# FPGA.net
KiCad netlist of a schematic drawn in Altium Designer
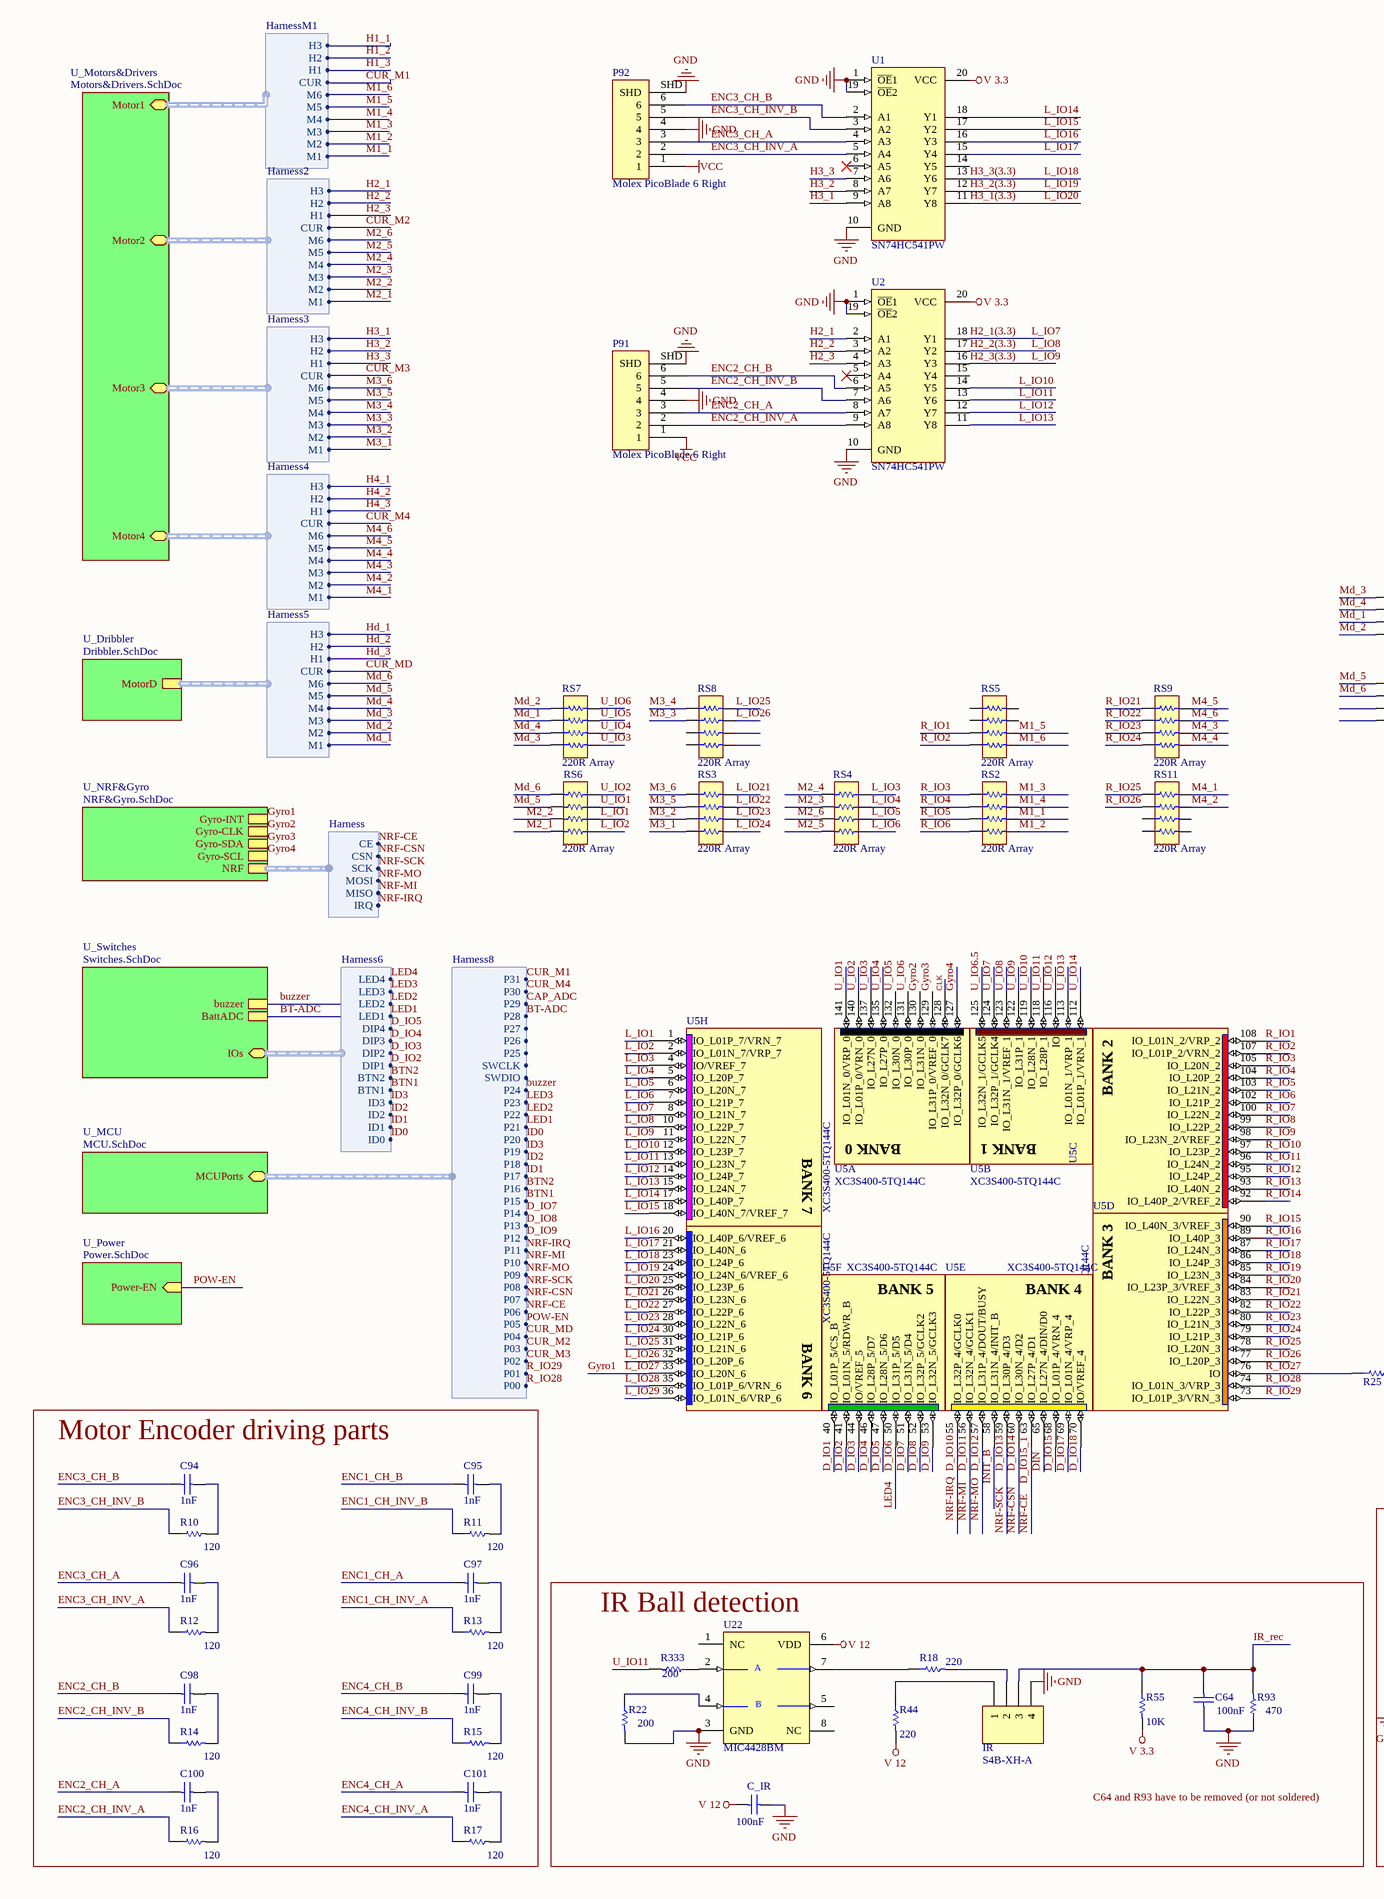
[diagram p0: FPGA.SchDoc, left]
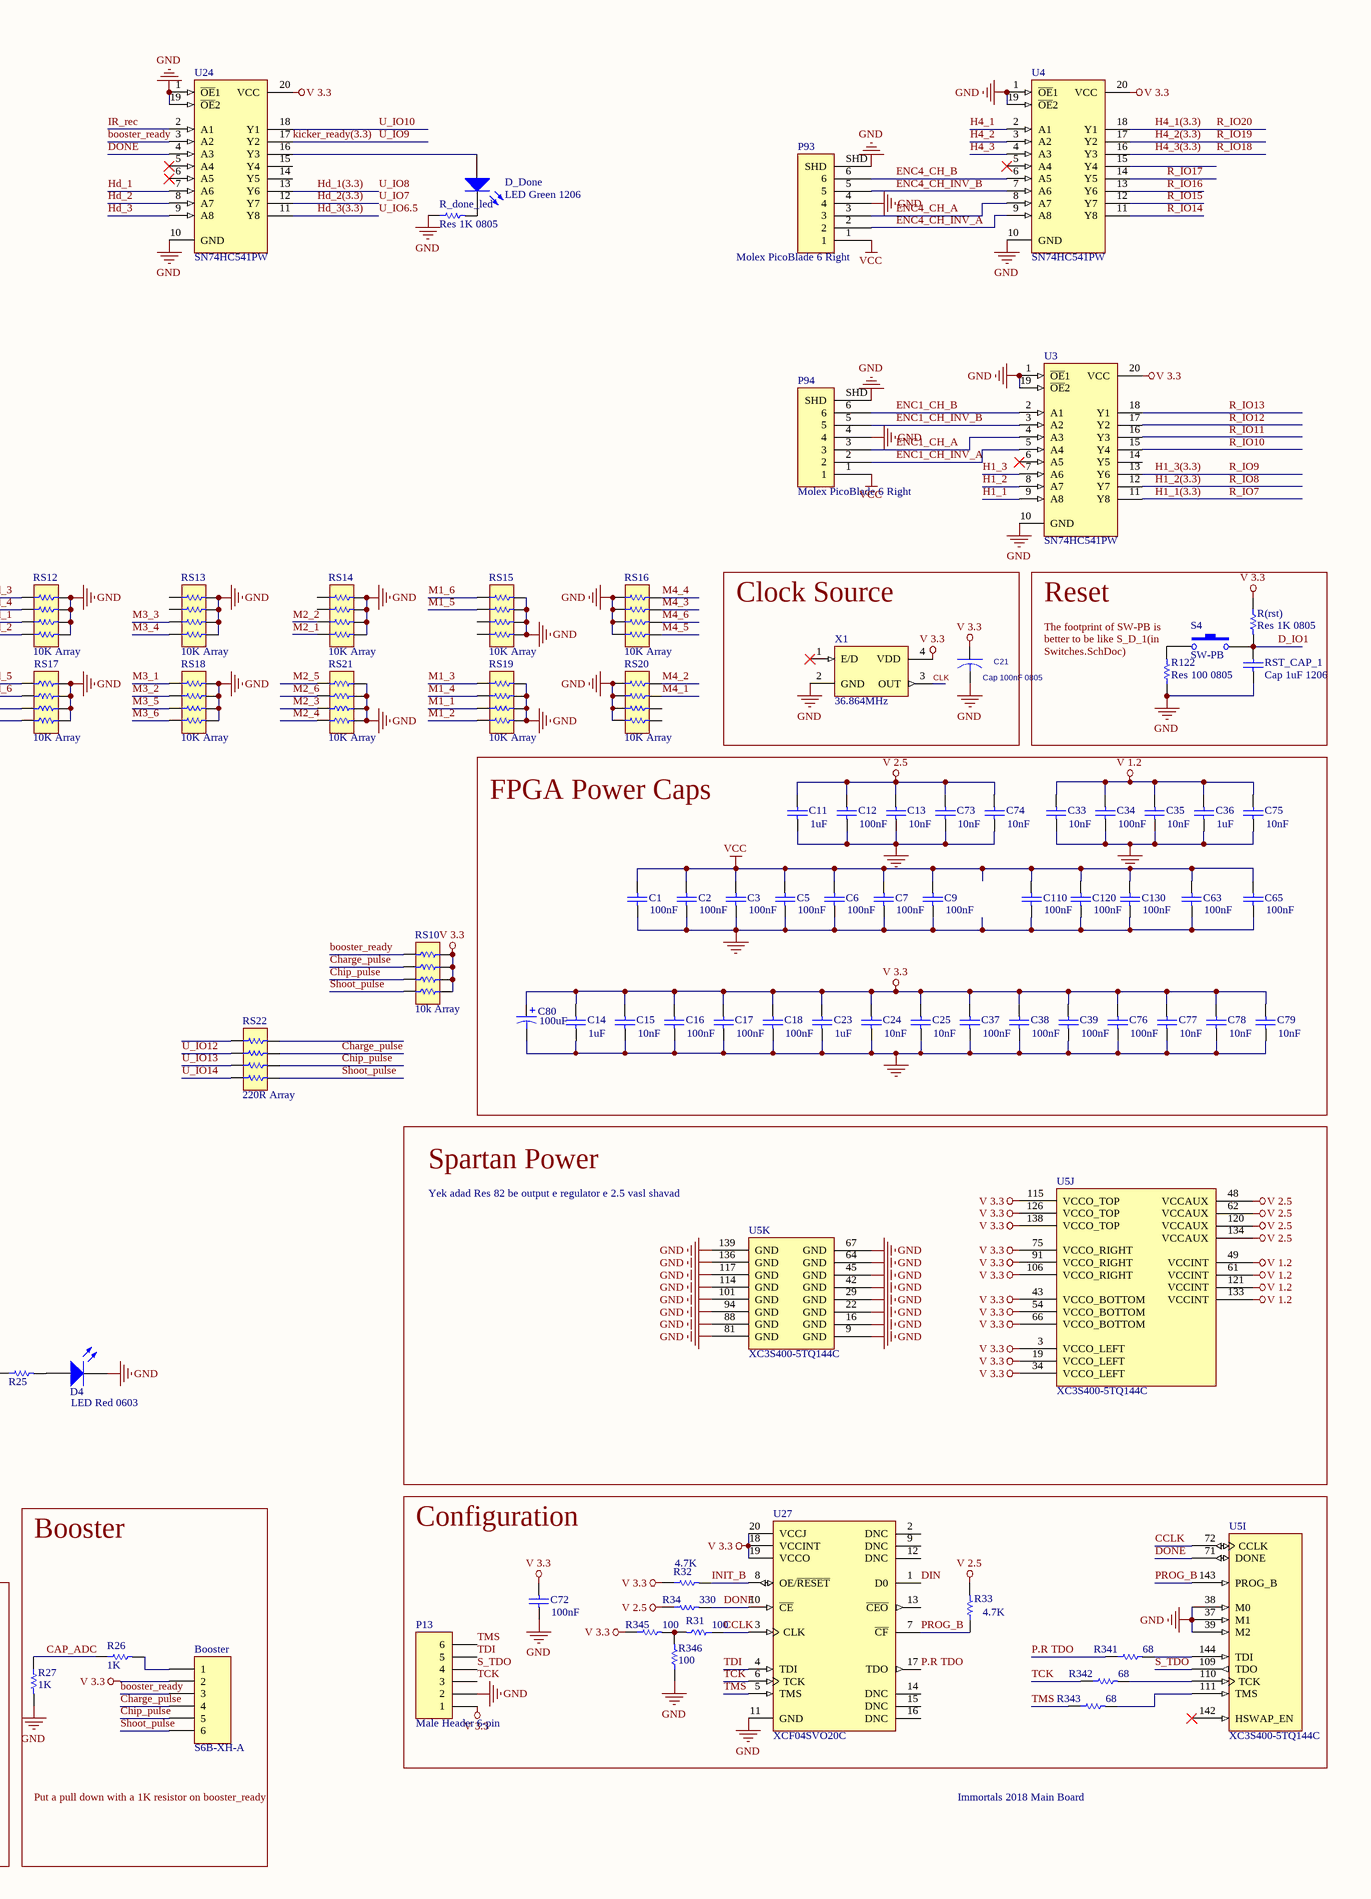
[diagram p1: FPGA.SchDoc, right]

(export (version "E")
  (design (tool "Eeschema 10.0.6"))
  (components
    (comp (ref "Booster")
      (value "S6B-XH-A")
      (footprint "S6B-XH-A")
      (description "Header, 6-Pin")
      (fields (field (name "PUBLISHER") "Altium Limited"))
      (libsource (lib "REV(5)") (part "Header 6"))
    )
    (comp (ref "C1")
      (value "100nF")
      (footprint "C1206")
      (description "Capacitor")
      (fields (field (name "Comment") "Cap 100nF 1206"))
      (libsource (lib "Altium Nanoboard Project") (part "CAP"))
    )
    (comp (ref "C2")
      (value "100nF")
      (footprint "C1206")
      (description "Capacitor")
      (fields (field (name "Comment") "Cap 100nF 1206"))
      (libsource (lib "Altium Nanoboard Project") (part "CAP"))
    )
    (comp (ref "C3")
      (value "100nF")
      (footprint "C1206")
      (description "Capacitor")
      (fields (field (name "Comment") "Cap 100nF 1206"))
      (libsource (lib "Altium Nanoboard Project") (part "CAP"))
    )
    (comp (ref "C5")
      (value "100nF")
      (footprint "C1206")
      (description "Capacitor")
      (fields (field (name "Comment") "Cap 100nF 1206"))
      (libsource (lib "Altium Nanoboard Project") (part "CAP"))
    )
    (comp (ref "C6")
      (value "100nF")
      (footprint "C1206")
      (description "Capacitor")
      (fields (field (name "Comment") "Cap 100nF 1206"))
      (libsource (lib "Altium Nanoboard Project") (part "CAP"))
    )
    (comp (ref "C7")
      (value "100nF")
      (footprint "C1206")
      (description "Capacitor")
      (fields (field (name "Comment") "Cap 100nF 1206"))
      (libsource (lib "Altium Nanoboard Project") (part "CAP"))
    )
    (comp (ref "C9")
      (value "100nF")
      (footprint "C1206")
      (description "Capacitor")
      (fields (field (name "Comment") "Cap 100nF 1206"))
      (libsource (lib "Altium Nanoboard Project") (part "CAP"))
    )
    (comp (ref "C11")
      (value "1uF")
      (footprint "1608[0603]")
      (description "Capacitor (Semiconductor SIM Model)")
      (fields (field (name "Comment") "Cap 1uF 0603") (field (name "PUBLISHER") "Altium Limited"))
      (libsource (lib "Miscellaneous Devices") (part "Cap Semi"))
    )
    (comp (ref "C12")
      (value "100nF")
      (footprint "1608[0603]")
      (description "Capacitor (Semiconductor SIM Model)")
      (fields (field (name "Comment") "Cap 100nF 0603") (field (name "PUBLISHER") "Altium Limited"))
      (libsource (lib "Miscellaneous Devices") (part "Cap Semi"))
    )
    (comp (ref "C13")
      (value "10nF")
      (footprint "1608[0603]")
      (description "Capacitor (Semiconductor SIM Model)")
      (fields (field (name "Comment") "Cap 10nF 0603") (field (name "PUBLISHER") "Altium Limited"))
      (libsource (lib "Miscellaneous Devices") (part "Cap Semi"))
    )
    (comp (ref "C14")
      (value "1uF")
      (footprint "1608[0603]")
      (description "Capacitor (Semiconductor SIM Model)")
      (fields (field (name "Comment") "Cap 1uF 0603") (field (name "PUBLISHER") "Altium Limited"))
      (libsource (lib "Miscellaneous Devices") (part "Cap Semi"))
    )
    (comp (ref "C15")
      (value "10nF")
      (footprint "1608[0603]")
      (description "Capacitor (Semiconductor SIM Model)")
      (fields (field (name "Comment") "Cap 10nF 0603") (field (name "PUBLISHER") "Altium Limited"))
      (libsource (lib "Miscellaneous Devices") (part "Cap Semi"))
    )
    (comp (ref "C16")
      (value "100nF")
      (footprint "1608[0603]")
      (description "Capacitor (Semiconductor SIM Model)")
      (fields (field (name "Comment") "Cap 100nF 0603") (field (name "PUBLISHER") "Altium Limited"))
      (libsource (lib "Miscellaneous Devices") (part "Cap Semi"))
    )
    (comp (ref "C17")
      (value "100nF")
      (footprint "1608[0603]")
      (description "Capacitor (Semiconductor SIM Model)")
      (fields (field (name "Comment") "Cap 100nF 0603") (field (name "PUBLISHER") "Altium Limited"))
      (libsource (lib "Miscellaneous Devices") (part "Cap Semi"))
    )
    (comp (ref "C18")
      (value "100nF")
      (footprint "1608[0603]")
      (description "Capacitor (Semiconductor SIM Model)")
      (fields (field (name "Comment") "Cap 100nF 0603") (field (name "PUBLISHER") "Altium Limited"))
      (libsource (lib "Miscellaneous Devices") (part "Cap Semi"))
    )
    (comp (ref "C21") (value "Cap 100nF 0805") (footprint "2012[0805]") (libsource (lib "*") (part "C_Dup1")))
    (comp (ref "C23")
      (value "1uF")
      (footprint "1608[0603]")
      (description "Capacitor (Semiconductor SIM Model)")
      (fields (field (name "Comment") "Cap 1uF 0603") (field (name "PUBLISHER") "Altium Limited"))
      (libsource (lib "Miscellaneous Devices") (part "Cap Semi"))
    )
    (comp (ref "C24")
      (value "10nF")
      (footprint "1608[0603]")
      (description "Capacitor (Semiconductor SIM Model)")
      (fields (field (name "Comment") "Cap 10nF 0603") (field (name "PUBLISHER") "Altium Limited"))
      (libsource (lib "Miscellaneous Devices") (part "Cap Semi"))
    )
    (comp (ref "C25")
      (value "10nF")
      (footprint "1608[0603]")
      (description "Capacitor (Semiconductor SIM Model)")
      (fields (field (name "Comment") "Cap 10nF 0603") (field (name "PUBLISHER") "Altium Limited"))
      (libsource (lib "Miscellaneous Devices") (part "Cap Semi"))
    )
    (comp (ref "C33")
      (value "10nF")
      (footprint "1608[0603]")
      (description "Capacitor (Semiconductor SIM Model)")
      (fields (field (name "Comment") "Cap 10nF 0603") (field (name "PUBLISHER") "Altium Limited"))
      (libsource (lib "Miscellaneous Devices") (part "Cap Semi"))
    )
    (comp (ref "C34")
      (value "100nF")
      (footprint "1608[0603]")
      (description "Capacitor (Semiconductor SIM Model)")
      (fields (field (name "Comment") "Cap 100nF 0603") (field (name "PUBLISHER") "Altium Limited"))
      (libsource (lib "Miscellaneous Devices") (part "Cap Semi"))
    )
    (comp (ref "C35")
      (value "10nF")
      (footprint "1608[0603]")
      (description "Capacitor (Semiconductor SIM Model)")
      (fields (field (name "Comment") "Cap 10nF 0603") (field (name "PUBLISHER") "Altium Limited"))
      (libsource (lib "Miscellaneous Devices") (part "Cap Semi"))
    )
    (comp (ref "C36")
      (value "1uF")
      (footprint "1608[0603]")
      (description "Capacitor (Semiconductor SIM Model)")
      (fields (field (name "Comment") "Cap 1uF 0603") (field (name "PUBLISHER") "Altium Limited"))
      (libsource (lib "Miscellaneous Devices") (part "Cap Semi"))
    )
    (comp (ref "C37")
      (value "100nF")
      (footprint "1608[0603]")
      (description "Capacitor (Semiconductor SIM Model)")
      (fields (field (name "Comment") "Cap 100nF 0603") (field (name "PUBLISHER") "Altium Limited"))
      (libsource (lib "Miscellaneous Devices") (part "Cap Semi"))
    )
    (comp (ref "C38")
      (value "100nF")
      (footprint "1608[0603]")
      (description "Capacitor (Semiconductor SIM Model)")
      (fields (field (name "Comment") "Cap 100nF 0603") (field (name "PUBLISHER") "Altium Limited"))
      (libsource (lib "Miscellaneous Devices") (part "Cap Semi"))
    )
    (comp (ref "C39")
      (value "100nF")
      (footprint "1608[0603]")
      (description "Capacitor (Semiconductor SIM Model)")
      (fields (field (name "Comment") "Cap 100nF 0603") (field (name "PUBLISHER") "Altium Limited"))
      (libsource (lib "Miscellaneous Devices") (part "Cap Semi"))
    )
    (comp (ref "C63")
      (value "100nF")
      (footprint "C0805")
      (description "Capacitor")
      (fields (field (name "Comment") "Cap 100nF 0805"))
      (libsource (lib "Altium Nanoboard Project") (part "CAP"))
    )
    (comp (ref "C64")
      (value "100nF")
      (footprint "1608[0603]")
      (description "Capacitor (Semiconductor SIM Model)")
      (fields (field (name "Comment") "Cap 100nF 0603") (field (name "PUBLISHER") "Altium Limited"))
      (libsource (lib "Miscellaneous Devices") (part "Cap Semi"))
    )
    (comp (ref "C65")
      (value "100nF")
      (footprint "C0805")
      (description "Capacitor")
      (fields (field (name "Comment") "Cap 100nF 0805"))
      (libsource (lib "Altium Nanoboard Project") (part "CAP"))
    )
    (comp (ref "C72")
      (value "100nF")
      (footprint "C0805")
      (description "Capacitor")
      (fields (field (name "Comment") "Cap 100nF 0805"))
      (libsource (lib "Altium Nanoboard Project") (part "CAP"))
    )
    (comp (ref "C73")
      (value "10nF")
      (footprint "1608[0603]")
      (description "Capacitor (Semiconductor SIM Model)")
      (fields (field (name "Comment") "Cap 10nF 0603") (field (name "PUBLISHER") "Altium Limited"))
      (libsource (lib "Miscellaneous Devices") (part "Cap Semi"))
    )
    (comp (ref "C74")
      (value "10nF")
      (footprint "1608[0603]")
      (description "Capacitor (Semiconductor SIM Model)")
      (fields (field (name "Comment") "Cap 10nF 0603") (field (name "PUBLISHER") "Altium Limited"))
      (libsource (lib "Miscellaneous Devices") (part "Cap Semi"))
    )
    (comp (ref "C75")
      (value "10nF")
      (footprint "1608[0603]")
      (description "Capacitor (Semiconductor SIM Model)")
      (fields (field (name "Comment") "Cap 10nF 0603") (field (name "PUBLISHER") "Altium Limited"))
      (libsource (lib "Miscellaneous Devices") (part "Cap Semi"))
    )
    (comp (ref "C76")
      (value "100nF")
      (footprint "1608[0603]")
      (description "Capacitor (Semiconductor SIM Model)")
      (fields (field (name "Comment") "Cap 100nF 0603") (field (name "PUBLISHER") "Altium Limited"))
      (libsource (lib "Miscellaneous Devices") (part "Cap Semi"))
    )
    (comp (ref "C77")
      (value "10nF")
      (footprint "1608[0603]")
      (description "Capacitor (Semiconductor SIM Model)")
      (fields (field (name "Comment") "Cap 10nF 0603") (field (name "PUBLISHER") "Altium Limited"))
      (libsource (lib "Miscellaneous Devices") (part "Cap Semi"))
    )
    (comp (ref "C78")
      (value "10nF")
      (footprint "1608[0603]")
      (description "Capacitor (Semiconductor SIM Model)")
      (fields (field (name "Comment") "Cap 10nF 0603") (field (name "PUBLISHER") "Altium Limited"))
      (libsource (lib "Miscellaneous Devices") (part "Cap Semi"))
    )
    (comp (ref "C79")
      (value "10nF")
      (footprint "1608[0603]")
      (description "Capacitor (Semiconductor SIM Model)")
      (fields (field (name "Comment") "Cap 10nF 0603") (field (name "PUBLISHER") "Altium Limited"))
      (libsource (lib "Miscellaneous Devices") (part "Cap Semi"))
    )
    (comp (ref "C80")
      (value "100uF")
      (footprint "6332[2512]")
      (description "Polarized Capacitor (Surface Mount)")
      (fields (field (name "Comment") "Cap 100uF 2512") (field (name "PUBLISHER") "Altium Limited"))
      (libsource (lib "Miscellaneous Devices") (part "Cap Pol3"))
    )
    (comp (ref "C94")
      (value "1nF")
      (footprint "1608[0603]")
      (description "Capacitor (Semiconductor SIM Model)")
      (fields (field (name "Comment") "Cap 1nF 0603") (field (name "PUBLISHER") "Altium Limited"))
      (libsource (lib "Miscellaneous Devices") (part "Cap Semi"))
    )
    (comp (ref "C95")
      (value "1nF")
      (footprint "1608[0603]")
      (description "Capacitor (Semiconductor SIM Model)")
      (fields (field (name "Comment") "Cap 1nF 0603") (field (name "PUBLISHER") "Altium Limited"))
      (libsource (lib "Miscellaneous Devices") (part "Cap Semi"))
    )
    (comp (ref "C96")
      (value "1nF")
      (footprint "1608[0603]")
      (description "Capacitor (Semiconductor SIM Model)")
      (fields (field (name "Comment") "Cap 1nF 0603") (field (name "PUBLISHER") "Altium Limited"))
      (libsource (lib "Miscellaneous Devices") (part "Cap Semi"))
    )
    (comp (ref "C97")
      (value "1nF")
      (footprint "1608[0603]")
      (description "Capacitor (Semiconductor SIM Model)")
      (fields (field (name "Comment") "Cap 1nF 0603") (field (name "PUBLISHER") "Altium Limited"))
      (libsource (lib "Miscellaneous Devices") (part "Cap Semi"))
    )
    (comp (ref "C98")
      (value "1nF")
      (footprint "1608[0603]")
      (description "Capacitor (Semiconductor SIM Model)")
      (fields (field (name "Comment") "Cap 1nF 0603") (field (name "PUBLISHER") "Altium Limited"))
      (libsource (lib "Miscellaneous Devices") (part "Cap Semi"))
    )
    (comp (ref "C99")
      (value "1nF")
      (footprint "1608[0603]")
      (description "Capacitor (Semiconductor SIM Model)")
      (fields (field (name "Comment") "Cap 1nF 0603") (field (name "PUBLISHER") "Altium Limited"))
      (libsource (lib "Miscellaneous Devices") (part "Cap Semi"))
    )
    (comp (ref "C100")
      (value "1nF")
      (footprint "1608[0603]")
      (description "Capacitor (Semiconductor SIM Model)")
      (fields (field (name "Comment") "Cap 1nF 0603") (field (name "PUBLISHER") "Altium Limited"))
      (libsource (lib "Miscellaneous Devices") (part "Cap Semi"))
    )
    (comp (ref "C101")
      (value "1nF")
      (footprint "1608[0603]")
      (description "Capacitor (Semiconductor SIM Model)")
      (fields (field (name "Comment") "Cap 1nF 0603") (field (name "PUBLISHER") "Altium Limited"))
      (libsource (lib "Miscellaneous Devices") (part "Cap Semi"))
    )
    (comp (ref "C110")
      (value "100nF")
      (footprint "C1206")
      (description "Capacitor")
      (fields (field (name "Comment") "Cap 100nF 1206"))
      (libsource (lib "Altium Nanoboard Project") (part "CAP"))
    )
    (comp (ref "C120")
      (value "100nF")
      (footprint "C1206")
      (description "Capacitor")
      (fields (field (name "Comment") "Cap 100nF 1206"))
      (libsource (lib "Altium Nanoboard Project") (part "CAP"))
    )
    (comp (ref "C130")
      (value "100nF")
      (footprint "C1206")
      (description "Capacitor")
      (fields (field (name "Comment") "Cap 100nF 1206"))
      (libsource (lib "Altium Nanoboard Project") (part "CAP"))
    )
    (comp (ref "C_IR")
      (value "100nF")
      (footprint "C0805")
      (description "Capacitor")
      (fields (field (name "Comment") "Cap 100nF 0805"))
      (libsource (lib "Altium Nanoboard Project") (part "CAP"))
    )
    (comp (ref "D4")
      (value "LED Red 0603")
      (footprint "LED 0603")
      (description "LED ,SMD ,0603")
      (fields (field (name "PUBLISHER") "Altium Limited"))
      (libsource (lib "SamatecLib") (part "LED 0603"))
    )
    (comp (ref "D_Done")
      (value "LED Green 1206")
      (footprint "3.2X1.6X1.1 - GREEN")
      (description "Typical RED, GREEN, YELLOW, AMBER GaAs LED")
      (fields (field (name "PUBLISHER") "Altium Limited"))
      (libsource (lib "Miscellaneous Devices") (part "LED2"))
    )
    (comp (ref "IR")
      (value "S4B-XH-A")
      (footprint "S4B-XH-A")
      (description "Header, 4-Pin")
      (fields (field (name "PUBLISHER") "Altium Limited"))
      (libsource (lib "REV(5)") (part "Header 4"))
    )
    (comp (ref "P13")
      (value "Male Header 6-pin")
      (footprint "HDR1X6")
      (description "Header, 6-Pin")
      (fields (field (name "PUBLISHER") "Altium Limited"))
      (libsource (lib "Miscellaneous Connectors") (part "Header 6"))
    )
    (comp (ref "P91")
      (value "Molex PicoBlade 6 Right")
      (footprint "Molex PicoBlade 6 Right SMD")
      (libsource (lib "SamatecLib") (part "Molex PicoBlade 6 Right"))
    )
    (comp (ref "P92")
      (value "Molex PicoBlade 6 Right")
      (footprint "Molex PicoBlade 6 Right SMD")
      (libsource (lib "SamatecLib") (part "Molex PicoBlade 6 Right"))
    )
    (comp (ref "P93")
      (value "Molex PicoBlade 6 Right")
      (footprint "Molex PicoBlade 6 Right SMD")
      (libsource (lib "SamatecLib") (part "Molex PicoBlade 6 Right"))
    )
    (comp (ref "P94")
      (value "Molex PicoBlade 6 Right")
      (footprint "Molex PicoBlade 6 Right SMD")
      (libsource (lib "SamatecLib") (part "Molex PicoBlade 6 Right"))
    )
    (comp (ref "R(rst)")
      (value "Res 1K 0805")
      (footprint "Miscellaneous Devices:2012[0805]")
      (description "Resistor")
      (fields (field (name "PUBLISHER") "Altium Limited"))
      (libsource (lib "Miscellaneous Devices") (part "Res1"))
    )
    (comp (ref "R10")
      (value "120")
      (footprint "1608[0603]")
      (description "Semiconductor Resistor")
      (fields (field (name "Comment") "Res 120 0603") (field (name "PUBLISHER") "Altium Limited"))
      (libsource (lib "Miscellaneous Devices") (part "Res Semi"))
    )
    (comp (ref "R11")
      (value "120")
      (footprint "1608[0603]")
      (description "Semiconductor Resistor")
      (fields (field (name "Comment") "Res 120 0603") (field (name "PUBLISHER") "Altium Limited"))
      (libsource (lib "Miscellaneous Devices") (part "Res Semi"))
    )
    (comp (ref "R12")
      (value "120")
      (footprint "1608[0603]")
      (description "Semiconductor Resistor")
      (fields (field (name "Comment") "Res 120 0603") (field (name "PUBLISHER") "Altium Limited"))
      (libsource (lib "Miscellaneous Devices") (part "Res Semi"))
    )
    (comp (ref "R13")
      (value "120")
      (footprint "1608[0603]")
      (description "Semiconductor Resistor")
      (fields (field (name "Comment") "Res 120 0603") (field (name "PUBLISHER") "Altium Limited"))
      (libsource (lib "Miscellaneous Devices") (part "Res Semi"))
    )
    (comp (ref "R14")
      (value "120")
      (footprint "1608[0603]")
      (description "Semiconductor Resistor")
      (fields (field (name "Comment") "Res 120 0603") (field (name "PUBLISHER") "Altium Limited"))
      (libsource (lib "Miscellaneous Devices") (part "Res Semi"))
    )
    (comp (ref "R15")
      (value "120")
      (footprint "1608[0603]")
      (description "Semiconductor Resistor")
      (fields (field (name "Comment") "Res 120 0603") (field (name "PUBLISHER") "Altium Limited"))
      (libsource (lib "Miscellaneous Devices") (part "Res Semi"))
    )
    (comp (ref "R16")
      (value "120")
      (footprint "1608[0603]")
      (description "Semiconductor Resistor")
      (fields (field (name "Comment") "Res 120 0603") (field (name "PUBLISHER") "Altium Limited"))
      (libsource (lib "Miscellaneous Devices") (part "Res Semi"))
    )
    (comp (ref "R17")
      (value "120")
      (footprint "1608[0603]")
      (description "Semiconductor Resistor")
      (fields (field (name "Comment") "Res 120 0603") (field (name "PUBLISHER") "Altium Limited"))
      (libsource (lib "Miscellaneous Devices") (part "Res Semi"))
    )
    (comp (ref "R18")
      (value "220")
      (footprint "2012[0805]")
      (description "Semiconductor Resistor")
      (fields (field (name "Comment") "Res 220 0805") (field (name "PUBLISHER") "Altium Limited"))
      (libsource (lib "Miscellaneous Devices") (part "Res Semi"))
    )
    (comp (ref "R22")
      (value "200")
      (footprint "2012[0805]")
      (description "Semiconductor Resistor")
      (fields (field (name "Comment") "Res 200 0805") (field (name "PUBLISHER") "Altium Limited"))
      (libsource (lib "Miscellaneous Devices") (part "Res Semi"))
    )
    (comp (ref "R25")
      (value "Res 330 0603")
      (footprint "R0603")
      (description "Res 0603")
      (libsource (lib "SamatecLib") (part "R0603"))
    )
    (comp (ref "R26")
      (value "1K")
      (footprint "2012[0805]")
      (description "Semiconductor Resistor")
      (fields (field (name "Comment") "Res 1K 0805") (field (name "PUBLISHER") "Altium Limited"))
      (libsource (lib "Miscellaneous Devices") (part "Res Semi"))
    )
    (comp (ref "R27")
      (value "1K")
      (footprint "2012[0805]")
      (description "Semiconductor Resistor")
      (fields (field (name "Comment") "Res 1K 0805") (field (name "PUBLISHER") "Altium Limited"))
      (libsource (lib "Miscellaneous Devices") (part "Res Semi"))
    )
    (comp (ref "R31")
      (value "100")
      (footprint "2012[0805]")
      (description "Semiconductor Resistor")
      (fields (field (name "Comment") "Res 100 0805") (field (name "PUBLISHER") "Altium Limited"))
      (libsource (lib "Miscellaneous Devices") (part "Res Semi"))
    )
    (comp (ref "R32")
      (value "4.7K")
      (footprint "2012[0805]")
      (description "Semiconductor Resistor")
      (fields (field (name "Comment") "Res 4.7K 0805") (field (name "PUBLISHER") "Altium Limited"))
      (libsource (lib "Miscellaneous Devices") (part "Res Semi"))
    )
    (comp (ref "R33")
      (value "4.7K")
      (footprint "2012[0805]")
      (description "Semiconductor Resistor")
      (fields (field (name "Comment") "Res 4.7K 0805") (field (name "PUBLISHER") "Altium Limited"))
      (libsource (lib "Miscellaneous Devices") (part "Res Semi"))
    )
    (comp (ref "R34")
      (value "330")
      (footprint "2012[0805]")
      (description "Semiconductor Resistor")
      (fields (field (name "Comment") "Res 330 0805") (field (name "PUBLISHER") "Altium Limited"))
      (libsource (lib "Miscellaneous Devices") (part "Res Semi"))
    )
    (comp (ref "R44")
      (value "220")
      (footprint "2012[0805]")
      (description "Semiconductor Resistor")
      (fields (field (name "Comment") "Res 220 0805") (field (name "PUBLISHER") "Altium Limited"))
      (libsource (lib "Miscellaneous Devices") (part "Res Semi"))
    )
    (comp (ref "R55")
      (value "10K")
      (footprint "2012[0805]")
      (description "Semiconductor Resistor")
      (fields (field (name "Comment") "Res 10K 0805") (field (name "PUBLISHER") "Altium Limited"))
      (libsource (lib "Miscellaneous Devices") (part "Res Semi"))
    )
    (comp (ref "R93")
      (value "470")
      (footprint "1608[0603]")
      (description "Semiconductor Resistor")
      (fields (field (name "Comment") "Res 470 0603") (field (name "PUBLISHER") "Altium Limited"))
      (libsource (lib "Miscellaneous Devices") (part "Res Semi"))
    )
    (comp (ref "R122")
      (value "Res 100 0805")
      (footprint "Miscellaneous Devices:2012[0805]")
      (description "Resistor")
      (fields (field (name "PUBLISHER") "Altium Limited"))
      (libsource (lib "Miscellaneous Devices") (part "Res1"))
    )
    (comp (ref "R333")
      (value "200")
      (footprint "2012[0805]")
      (description "Semiconductor Resistor")
      (fields (field (name "Comment") "Res 200 0805") (field (name "PUBLISHER") "Altium Limited"))
      (libsource (lib "Miscellaneous Devices") (part "Res Semi"))
    )
    (comp (ref "R341")
      (value "68")
      (footprint "2012[0805]")
      (description "Semiconductor Resistor")
      (fields (field (name "Comment") "Res 68 0805") (field (name "PUBLISHER") "Altium Limited"))
      (libsource (lib "Miscellaneous Devices") (part "Res Semi"))
    )
    (comp (ref "R342")
      (value "68")
      (footprint "2012[0805]")
      (description "Semiconductor Resistor")
      (fields (field (name "Comment") "Res 68 0805") (field (name "PUBLISHER") "Altium Limited"))
      (libsource (lib "Miscellaneous Devices") (part "Res Semi"))
    )
    (comp (ref "R343")
      (value "68")
      (footprint "2012[0805]")
      (description "Semiconductor Resistor")
      (fields (field (name "Comment") "Res 68 0805") (field (name "PUBLISHER") "Altium Limited"))
      (libsource (lib "Miscellaneous Devices") (part "Res Semi"))
    )
    (comp (ref "R345")
      (value "100")
      (footprint "2012[0805]")
      (description "Semiconductor Resistor")
      (fields (field (name "Comment") "Res 100 0805") (field (name "PUBLISHER") "Altium Limited"))
      (libsource (lib "Miscellaneous Devices") (part "Res Semi"))
    )
    (comp (ref "R346")
      (value "100")
      (footprint "2012[0805]")
      (description "Semiconductor Resistor")
      (fields (field (name "Comment") "Res 100 0805") (field (name "PUBLISHER") "Altium Limited"))
      (libsource (lib "Miscellaneous Devices") (part "Res Semi"))
    )
    (comp (ref "RS2")
      (value "220R Array")
      (footprint "RES-4B")
      (description "Resistor Array ,SMD")
      (libsource (lib "") (part "Resister Array_1"))
    )
    (comp (ref "RS3")
      (value "220R Array")
      (footprint "RES-4B")
      (description "Resistor Array ,SMD")
      (libsource (lib "") (part "Resister Array_1"))
    )
    (comp (ref "RS4")
      (value "220R Array")
      (footprint "RES-4B")
      (description "Resistor Array ,SMD")
      (libsource (lib "SamatecLib") (part "Resister Array"))
    )
    (comp (ref "RS5")
      (value "220R Array")
      (footprint "RES-4B")
      (description "Resistor Array ,SMD")
      (libsource (lib "") (part "Resister Array_1"))
    )
    (comp (ref "RS6")
      (value "220R Array")
      (footprint "RES-4B")
      (description "Resistor Array ,SMD")
      (libsource (lib "SamatecLib") (part "Resister Array"))
    )
    (comp (ref "RS7")
      (value "220R Array")
      (footprint "RES-4B")
      (description "Resistor Array ,SMD")
      (libsource (lib "") (part "Resister Array_1"))
    )
    (comp (ref "RS8")
      (value "220R Array")
      (footprint "RES-4B")
      (description "Resistor Array ,SMD")
      (libsource (lib "") (part "Resister Array_1"))
    )
    (comp (ref "RS9")
      (value "220R Array")
      (footprint "RES-4B")
      (description "Resistor Array ,SMD")
      (libsource (lib "") (part "Resister Array_1"))
    )
    (comp (ref "RS10")
      (value "10k Array")
      (footprint "RES-4B")
      (description "Resistor Array ,SMD")
      (libsource (lib "SamatecLib") (part "Resister Array"))
    )
    (comp (ref "RS11")
      (value "220R Array")
      (footprint "RES-4B")
      (description "Resistor Array ,SMD")
      (libsource (lib "") (part "Resister Array_1"))
    )
    (comp (ref "RS12")
      (value "10K Array")
      (footprint "RES-4B")
      (description "Resistor Array ,SMD")
      (libsource (lib "") (part "Resister Array_1"))
    )
    (comp (ref "RS13")
      (value "10K Array")
      (footprint "RES-4B")
      (description "Resistor Array ,SMD")
      (libsource (lib "") (part "Resister Array_1"))
    )
    (comp (ref "RS14")
      (value "10K Array")
      (footprint "RES-4B")
      (description "Resistor Array ,SMD")
      (libsource (lib "") (part "Resister Array_1"))
    )
    (comp (ref "RS15")
      (value "10K Array")
      (footprint "RES-4B")
      (description "Resistor Array ,SMD")
      (libsource (lib "") (part "Resister Array_1"))
    )
    (comp (ref "RS16")
      (value "10K Array")
      (footprint "RES-4B")
      (description "Resistor Array ,SMD")
      (libsource (lib "") (part "Resister Array_1"))
    )
    (comp (ref "RS17")
      (value "10K Array")
      (footprint "RES-4B")
      (description "Resistor Array ,SMD")
      (libsource (lib "SamatecLib") (part "Resister Array"))
    )
    (comp (ref "RS18")
      (value "10K Array")
      (footprint "RES-4B")
      (description "Resistor Array ,SMD")
      (libsource (lib "") (part "Resister Array_1"))
    )
    (comp (ref "RS19")
      (value "10K Array")
      (footprint "RES-4B")
      (description "Resistor Array ,SMD")
      (libsource (lib "") (part "Resister Array_1"))
    )
    (comp (ref "RS20")
      (value "10K Array")
      (footprint "RES-4B")
      (description "Resistor Array ,SMD")
      (libsource (lib "") (part "Resister Array_1"))
    )
    (comp (ref "RS21")
      (value "10K Array")
      (footprint "RES-4B")
      (description "Resistor Array ,SMD")
      (libsource (lib "SamatecLib") (part "Resister Array"))
    )
    (comp (ref "RS22")
      (value "220R Array")
      (footprint "RES-4B")
      (description "Resistor Array ,SMD")
      (libsource (lib "") (part "Resister Array_1"))
    )
    (comp (ref "RST_CAP_1")
      (value "Cap 1uF 1206")
      (footprint "3216[1206]")
      (description "Capacitor")
      (fields (field (name "PUBLISHER") "Altium Limited"))
      (libsource (lib "Miscellaneous Devices") (part "Cap"))
    )
    (comp (ref "R_done_led")
      (value "Res 1K 0805")
      (footprint "2012[0805]")
      (description "Semiconductor Resistor")
      (fields (field (name "PUBLISHER") "Altium Limited"))
      (libsource (lib "Miscellaneous Devices") (part "Res Semi"))
    )
    (comp (ref "S4")
      (value "SW-PB")
      (footprint "SPST-2")
      (description "Switch")
      (fields (field (name "PUBLISHER") "Altium Limited"))
      (libsource (lib "Miscellaneous Devices") (part "SW-PB"))
    )
    (comp (ref "U1")
      (value "SN74HC541PW")
      (footprint "PW020_N")
      (description "Octal Buffer/Driver with 3-State Outputs")
      (fields (field (name "PUBLISHER") "Altium Limited"))
      (libsource (lib "REV(5)") (part "SN74HC541PW"))
    )
    (comp (ref "U2")
      (value "SN74HC541PW")
      (footprint "PW020_N")
      (description "Octal Buffer/Driver with 3-State Outputs")
      (fields (field (name "PUBLISHER") "Altium Limited"))
      (libsource (lib "REV(5)") (part "SN74HC541PW"))
    )
    (comp (ref "U3")
      (value "SN74HC541PW")
      (footprint "PW020_N")
      (description "Octal Buffer/Driver with 3-State Outputs")
      (fields (field (name "PUBLISHER") "Altium Limited"))
      (libsource (lib "REV(5)") (part "SN74HC541PW"))
    )
    (comp (ref "U4")
      (value "SN74HC541PW")
      (footprint "PW020_N")
      (description "Octal Buffer/Driver with 3-State Outputs")
      (fields (field (name "PUBLISHER") "Altium Limited"))
      (libsource (lib "REV(5)") (part "SN74HC541PW"))
    )
    (comp (ref "U5")
      (value "XC3S400-5TQ144C")
      (footprint "TQ144_L")
      (description "Spartan-3 1.2V FPGA, 97 User I/Os, 144-Pin TQFP, High Performance, Commercial Grade")
      (fields (field (name "PUBLISHER") "Altium Limited"))
      (libsource (lib "") (part "XC3S400-5TQ144C_2"))
    )
    (comp (ref "U22")
      (value "MIC4428BM")
      (footprint "NSO8_L")
      (description "Dual High-Speed 1.5A MOSFET Driver")
      (fields (field (name "PUBLISHER") "Altium Limited"))
      (libsource (lib "Maxim Interface MOSFET Driver") (part "MAX4427CSA"))
    )
    (comp (ref "U24")
      (value "SN74HC541PW")
      (footprint "PW020_N")
      (description "Octal Buffer/Driver with 3-State Outputs")
      (fields (field (name "PUBLISHER") "Altium Limited"))
      (libsource (lib "REV(5)") (part "SN74HC541PW"))
    )
    (comp (ref "U27")
      (value "XCF04SVO20C")
      (footprint "VO20_N")
      (fields (field (name "PUBLISHER") "Altium Limited"))
      (libsource (lib "Xilinx XCF") (part "XCF04SVO20C"))
    )
    (comp (ref "X1")
      (value "36.864MHz")
      (footprint "QSMO_4200")
      (description "QSMO - 4200 SERIES, 40MHz, SURFACE MOUNT CRYSTAL OSCILLATOR")
      (fields (field (name "PUBLISHER") "Altium Limited"))
      (libsource (lib "Altium Nanoboard Project") (part "QSMO_4200"))
    )
  )
  (nets
    (net (code "12") (name "/CAP_ADC") (class "Default")
      (node (ref "R26") (pin "1") (pinfunction "1_1") (pintype "passive"))
      (node (ref "R27") (pin "1") (pinfunction "1_1") (pintype "passive"))
    )
    (net (code "13") (name "/CCLK") (class "Default")
      (node (ref "R31") (pin "1") (pinfunction "1_1") (pintype "passive"))
      (node (ref "U27") (pin "3") (pinfunction "CLK_3") (pintype "input"))
      (node (ref "U5") (pin "72") (pinfunction "CCLK_72") (pintype "bidirectional"))
    )
    (net (code "14") (name "/CLK") (class "Default")
      (node (ref "U5") (pin "128") (pinfunction "IO_L32N_0/GCLK7_128") (pintype "bidirectional"))
      (node (ref "X1") (pin "3") (pinfunction "OUT_3") (pintype "output"))
    )
    (net (code "20") (name "/Charge_pulse") (class "Default")
      (node (ref "Booster") (pin "4") (pinfunction "4_4") (pintype "passive"))
      (node (ref "RS10") (pin "6") (pinfunction "6_6") (pintype "passive"))
      (node (ref "RS22") (pin "4") (pinfunction "4_4") (pintype "passive"))
    )
    (net (code "21") (name "/Chip_pulse") (class "Default")
      (node (ref "Booster") (pin "5") (pinfunction "5_5") (pintype "passive"))
      (node (ref "RS10") (pin "4") (pinfunction "4_4") (pintype "passive"))
      (node (ref "RS22") (pin "6") (pinfunction "6_6") (pintype "passive"))
    )
    (net (code "22") (name "/DIN") (class "Default")
      (node (ref "U27") (pin "1") (pinfunction "D0_1") (pintype "tri_state"))
      (node (ref "U5") (pin "65") (pinfunction "IO_L27N_4/DIN/D0_65") (pintype "bidirectional"))
    )
    (net (code "23") (name "/DONE") (class "Default")
      (node (ref "R34") (pin "2") (pinfunction "2_2") (pintype "passive"))
      (node (ref "U24") (pin "4") (pinfunction "A3_4") (pintype "input"))
      (node (ref "U27") (pin "10") (pinfunction "~{CE}_10") (pintype "input"))
      (node (ref "U5") (pin "71") (pinfunction "DONE_71") (pintype "bidirectional"))
    )
    (net (code "24") (name "/D_IO1") (class "Default")
      (node (ref "R(rst)") (pin "2") (pinfunction "2_2") (pintype "passive"))
      (node (ref "RST_CAP_1") (pin "2") (pinfunction "2_2") (pintype "passive"))
      (node (ref "S4") (pin "2") (pinfunction "2_2") (pintype "passive"))
      (node (ref "U5") (pin "40") (pinfunction "IO_L01P_5/CS_B_40") (pintype "bidirectional"))
    )
    (net (code "25") (name "/D_IO2") (class "Default")
      (node (ref "U5") (pin "41") (pinfunction "IO_L01N_5/RDWR_B_41") (pintype "bidirectional"))
    )
    (net (code "26") (name "/D_IO3") (class "Default")
      (node (ref "U5") (pin "44") (pinfunction "IO/VREF_5_44") (pintype "bidirectional"))
    )
    (net (code "27") (name "/D_IO4") (class "Default")
      (node (ref "U5") (pin "46") (pinfunction "IO_L28P_5/D7_46") (pintype "bidirectional"))
    )
    (net (code "28") (name "/D_IO5") (class "Default")
      (node (ref "U5") (pin "47") (pinfunction "IO_L28N_5/D6_47") (pintype "bidirectional"))
    )
    (net (code "29") (name "/D_IO6") (class "Default")
      (node (ref "U5") (pin "50") (pinfunction "IO_L31P_5/D5_50") (pintype "bidirectional"))
    )
    (net (code "30") (name "/D_IO7") (class "Default")
      (node (ref "U5") (pin "51") (pinfunction "IO_L31N_5/D4_51") (pintype "bidirectional"))
    )
    (net (code "31") (name "/D_IO8") (class "Default")
      (node (ref "U5") (pin "52") (pinfunction "IO_L32P_5/GCLK2_52") (pintype "bidirectional"))
    )
    (net (code "32") (name "/D_IO9") (class "Default")
      (node (ref "U5") (pin "53") (pinfunction "IO_L32N_5/GCLK3_53") (pintype "bidirectional"))
    )
    (net (code "33") (name "/D_IO10") (class "Default")
      (node (ref "U5") (pin "55") (pinfunction "IO_L32P_4/GCLK0_55") (pintype "bidirectional"))
    )
    (net (code "34") (name "/D_IO11") (class "Default")
      (node (ref "U5") (pin "56") (pinfunction "IO_L32N_4/GCLK1_56") (pintype "bidirectional"))
    )
    (net (code "35") (name "/D_IO12") (class "Default")
      (node (ref "U5") (pin "57") (pinfunction "IO_L31P_4/DOUT/BUSY_57") (pintype "bidirectional"))
    )
    (net (code "36") (name "/D_IO13") (class "Default")
      (node (ref "U5") (pin "59") (pinfunction "IO_L30P_4/D3_59") (pintype "bidirectional"))
    )
    (net (code "37") (name "/D_IO14") (class "Default")
      (node (ref "U5") (pin "60") (pinfunction "IO_L30N_4/D2_60") (pintype "bidirectional"))
    )
    (net (code "38") (name "/D_IO15") (class "Default")
      (node (ref "U5") (pin "68") (pinfunction "IO_L01P_4/VRN_4_68") (pintype "bidirectional"))
    )
    (net (code "39") (name "/D_IO15_1") (class "Default")
      (node (ref "U5") (pin "63") (pinfunction "IO_L27P_4/D1_63") (pintype "bidirectional"))
    )
    (net (code "40") (name "/D_IO17") (class "Default")
      (node (ref "U5") (pin "69") (pinfunction "IO_L01N_4/VRP_4_69") (pintype "bidirectional"))
    )
    (net (code "41") (name "/D_IO18") (class "Default")
      (node (ref "U5") (pin "70") (pinfunction "IO/VREF_4_70") (pintype "bidirectional"))
    )
    (net (code "42") (name "/ENC1_CH_A") (class "Default")
      (node (ref "C97") (pin "2") (pinfunction "2_2") (pintype "passive"))
      (node (ref "P94") (pin "3") (pinfunction "3_3") (pintype "passive"))
      (node (ref "U3") (pin "4") (pinfunction "A3_4") (pintype "input"))
    )
    (net (code "43") (name "/ENC1_CH_B") (class "Default")
      (node (ref "C95") (pin "2") (pinfunction "2_2") (pintype "passive"))
      (node (ref "P94") (pin "6") (pinfunction "6_6") (pintype "passive"))
      (node (ref "U3") (pin "2") (pinfunction "A1_2") (pintype "input"))
    )
    (net (code "44") (name "/ENC1_CH_INV_A") (class "Default")
      (node (ref "P94") (pin "2") (pinfunction "2_2") (pintype "passive"))
      (node (ref "R13") (pin "1") (pinfunction "1_1") (pintype "passive"))
      (node (ref "U3") (pin "5") (pinfunction "A4_5") (pintype "input"))
    )
    (net (code "45") (name "/ENC1_CH_INV_B") (class "Default")
      (node (ref "P94") (pin "5") (pinfunction "5_5") (pintype "passive"))
      (node (ref "R11") (pin "1") (pinfunction "1_1") (pintype "passive"))
      (node (ref "U3") (pin "3") (pinfunction "A2_3") (pintype "input"))
    )
    (net (code "46") (name "/ENC2_CH_A") (class "Default")
      (node (ref "C100") (pin "2") (pinfunction "2_2") (pintype "passive"))
      (node (ref "P91") (pin "3") (pinfunction "3_3") (pintype "passive"))
      (node (ref "U2") (pin "8") (pinfunction "A7_8") (pintype "input"))
    )
    (net (code "47") (name "/ENC2_CH_B") (class "Default")
      (node (ref "C98") (pin "2") (pinfunction "2_2") (pintype "passive"))
      (node (ref "P91") (pin "6") (pinfunction "6_6") (pintype "passive"))
      (node (ref "U2") (pin "6") (pinfunction "A5_6") (pintype "input"))
    )
    (net (code "48") (name "/ENC2_CH_INV_A") (class "Default")
      (node (ref "P91") (pin "2") (pinfunction "2_2") (pintype "passive"))
      (node (ref "R16") (pin "1") (pinfunction "1_1") (pintype "passive"))
      (node (ref "U2") (pin "9") (pinfunction "A8_9") (pintype "input"))
    )
    (net (code "49") (name "/ENC2_CH_INV_B") (class "Default")
      (node (ref "P91") (pin "5") (pinfunction "5_5") (pintype "passive"))
      (node (ref "R14") (pin "1") (pinfunction "1_1") (pintype "passive"))
      (node (ref "U2") (pin "7") (pinfunction "A6_7") (pintype "input"))
    )
    (net (code "50") (name "/ENC3_CH_A") (class "Default")
      (node (ref "C96") (pin "2") (pinfunction "2_2") (pintype "passive"))
      (node (ref "P92") (pin "3") (pinfunction "3_3") (pintype "passive"))
      (node (ref "U1") (pin "4") (pinfunction "A3_4") (pintype "input"))
    )
    (net (code "51") (name "/ENC3_CH_B") (class "Default")
      (node (ref "C94") (pin "2") (pinfunction "2_2") (pintype "passive"))
      (node (ref "P92") (pin "6") (pinfunction "6_6") (pintype "passive"))
      (node (ref "U1") (pin "2") (pinfunction "A1_2") (pintype "input"))
    )
    (net (code "52") (name "/ENC3_CH_INV_A") (class "Default")
      (node (ref "P92") (pin "2") (pinfunction "2_2") (pintype "passive"))
      (node (ref "R12") (pin "1") (pinfunction "1_1") (pintype "passive"))
      (node (ref "U1") (pin "5") (pinfunction "A4_5") (pintype "input"))
    )
    (net (code "53") (name "/ENC3_CH_INV_B") (class "Default")
      (node (ref "P92") (pin "5") (pinfunction "5_5") (pintype "passive"))
      (node (ref "R10") (pin "1") (pinfunction "1_1") (pintype "passive"))
      (node (ref "U1") (pin "3") (pinfunction "A2_3") (pintype "input"))
    )
    (net (code "54") (name "/ENC4_CH_A") (class "Default")
      (node (ref "C101") (pin "2") (pinfunction "2_2") (pintype "passive"))
      (node (ref "P93") (pin "3") (pinfunction "3_3") (pintype "passive"))
      (node (ref "U4") (pin "8") (pinfunction "A7_8") (pintype "input"))
    )
    (net (code "55") (name "/ENC4_CH_B") (class "Default")
      (node (ref "C99") (pin "2") (pinfunction "2_2") (pintype "passive"))
      (node (ref "P93") (pin "6") (pinfunction "6_6") (pintype "passive"))
      (node (ref "U4") (pin "6") (pinfunction "A5_6") (pintype "input"))
    )
    (net (code "56") (name "/ENC4_CH_INV_A") (class "Default")
      (node (ref "P93") (pin "2") (pinfunction "2_2") (pintype "passive"))
      (node (ref "R17") (pin "1") (pinfunction "1_1") (pintype "passive"))
      (node (ref "U4") (pin "9") (pinfunction "A8_9") (pintype "input"))
    )
    (net (code "57") (name "/ENC4_CH_INV_B") (class "Default")
      (node (ref "P93") (pin "5") (pinfunction "5_5") (pintype "passive"))
      (node (ref "R15") (pin "1") (pinfunction "1_1") (pintype "passive"))
      (node (ref "U4") (pin "7") (pinfunction "A6_7") (pintype "input"))
    )
    (net (code "58") (name "/Gyro1") (class "Default")
      (node (ref "U5") (pin "33") (pinfunction "IO_L20N_6_33") (pintype "bidirectional"))
    )
    (net (code "59") (name "/Gyro2") (class "Default")
      (node (ref "U5") (pin "130") (pinfunction "IO_L31N_0_130") (pintype "bidirectional"))
    )
    (net (code "60") (name "/Gyro3") (class "Default")
      (node (ref "U5") (pin "129") (pinfunction "IO_L31P_0/VREF_0_129") (pintype "bidirectional"))
    )
    (net (code "61") (name "/Gyro4") (class "Default")
      (node (ref "U5") (pin "127") (pinfunction "IO_L32P_0/GCLK6_127") (pintype "bidirectional"))
    )
    (net (code "62") (name "/H1_1") (class "Default")
      (node (ref "U3") (pin "9") (pinfunction "A8_9") (pintype "input"))
    )
    (net (code "63") (name "/H1_1(3.3)") (class "Default")
      (node (ref "U3") (pin "11") (pinfunction "Y8_11") (pintype "tri_state"))
      (node (ref "U5") (pin "100") (pinfunction "IO_L22N_2_100") (pintype "bidirectional"))
    )
    (net (code "64") (name "/H1_2") (class "Default")
      (node (ref "U3") (pin "8") (pinfunction "A7_8") (pintype "input"))
    )
    (net (code "65") (name "/H1_2(3.3)") (class "Default")
      (node (ref "U3") (pin "12") (pinfunction "Y7_12") (pintype "tri_state"))
      (node (ref "U5") (pin "99") (pinfunction "IO_L22P_2_99") (pintype "bidirectional"))
    )
    (net (code "66") (name "/H1_3") (class "Default")
      (node (ref "U3") (pin "7") (pinfunction "A6_7") (pintype "input"))
    )
    (net (code "67") (name "/H1_3(3.3)") (class "Default")
      (node (ref "U3") (pin "13") (pinfunction "Y6_13") (pintype "tri_state"))
      (node (ref "U5") (pin "98") (pinfunction "IO_L23N_2/VREF_2_98") (pintype "bidirectional"))
    )
    (net (code "68") (name "/H2_1") (class "Default")
      (node (ref "U2") (pin "2") (pinfunction "A1_2") (pintype "input"))
    )
    (net (code "69") (name "/H2_1(3.3)") (class "Default")
      (node (ref "U2") (pin "18") (pinfunction "Y1_18") (pintype "tri_state"))
      (node (ref "U5") (pin "8") (pinfunction "IO_L21N_7_8") (pintype "bidirectional"))
    )
    (net (code "70") (name "/H2_2") (class "Default")
      (node (ref "U2") (pin "3") (pinfunction "A2_3") (pintype "input"))
    )
    (net (code "71") (name "/H2_2(3.3)") (class "Default")
      (node (ref "U2") (pin "17") (pinfunction "Y2_17") (pintype "tri_state"))
      (node (ref "U5") (pin "10") (pinfunction "IO_L22P_7_10") (pintype "bidirectional"))
    )
    (net (code "72") (name "/H2_3") (class "Default")
      (node (ref "U2") (pin "4") (pinfunction "A3_4") (pintype "input"))
    )
    (net (code "73") (name "/H2_3(3.3)") (class "Default")
      (node (ref "U2") (pin "16") (pinfunction "Y3_16") (pintype "tri_state"))
      (node (ref "U5") (pin "11") (pinfunction "IO_L22N_7_11") (pintype "bidirectional"))
    )
    (net (code "74") (name "/H3_1") (class "Default")
      (node (ref "U1") (pin "9") (pinfunction "A8_9") (pintype "input"))
    )
    (net (code "75") (name "/H3_1(3.3)") (class "Default")
      (node (ref "U1") (pin "11") (pinfunction "Y8_11") (pintype "tri_state"))
      (node (ref "U5") (pin "25") (pinfunction "IO_L23P_6_25") (pintype "bidirectional"))
    )
    (net (code "76") (name "/H3_2") (class "Default")
      (node (ref "U1") (pin "8") (pinfunction "A7_8") (pintype "input"))
    )
    (net (code "77") (name "/H3_2(3.3)") (class "Default")
      (node (ref "U1") (pin "12") (pinfunction "Y7_12") (pintype "tri_state"))
      (node (ref "U5") (pin "24") (pinfunction "IO_L24N_6/VREF_6_24") (pintype "bidirectional"))
    )
    (net (code "78") (name "/H3_3") (class "Default")
      (node (ref "U1") (pin "7") (pinfunction "A6_7") (pintype "input"))
    )
    (net (code "79") (name "/H3_3(3.3)") (class "Default")
      (node (ref "U1") (pin "13") (pinfunction "Y6_13") (pintype "tri_state"))
      (node (ref "U5") (pin "23") (pinfunction "IO_L24P_6_23") (pintype "bidirectional"))
    )
    (net (code "80") (name "/H4_1") (class "Default")
      (node (ref "U4") (pin "2") (pinfunction "A1_2") (pintype "input"))
    )
    (net (code "81") (name "/H4_1(3.3)") (class "Default")
      (node (ref "U4") (pin "18") (pinfunction "Y1_18") (pintype "tri_state"))
      (node (ref "U5") (pin "84") (pinfunction "IO_L23P_3/VREF_3_84") (pintype "bidirectional"))
    )
    (net (code "82") (name "/H4_2") (class "Default")
      (node (ref "U4") (pin "3") (pinfunction "A2_3") (pintype "input"))
    )
    (net (code "83") (name "/H4_2(3.3)") (class "Default")
      (node (ref "U4") (pin "17") (pinfunction "Y2_17") (pintype "tri_state"))
      (node (ref "U5") (pin "85") (pinfunction "IO_L23N_3_85") (pintype "bidirectional"))
    )
    (net (code "84") (name "/H4_3") (class "Default")
      (node (ref "U4") (pin "4") (pinfunction "A3_4") (pintype "input"))
    )
    (net (code "85") (name "/H4_3(3.3)") (class "Default")
      (node (ref "U4") (pin "16") (pinfunction "Y3_16") (pintype "tri_state"))
      (node (ref "U5") (pin "86") (pinfunction "IO_L24P_3_86") (pintype "bidirectional"))
    )
    (net (code "86") (name "/Hd_1") (class "Default")
      (node (ref "U24") (pin "7") (pinfunction "A6_7") (pintype "input"))
    )
    (net (code "87") (name "/Hd_1(3.3)") (class "Default")
      (node (ref "U24") (pin "13") (pinfunction "Y6_13") (pintype "tri_state"))
      (node (ref "U5") (pin "123") (pinfunction "IO_L31N_1/VREF_1_123") (pintype "bidirectional"))
    )
    (net (code "88") (name "/Hd_2") (class "Default")
      (node (ref "U24") (pin "8") (pinfunction "A7_8") (pintype "input"))
    )
    (net (code "89") (name "/Hd_2(3.3)") (class "Default")
      (node (ref "U24") (pin "12") (pinfunction "Y7_12") (pintype "tri_state"))
      (node (ref "U5") (pin "124") (pinfunction "IO_L32P_1/GCLK4_124") (pintype "bidirectional"))
    )
    (net (code "90") (name "/Hd_3") (class "Default")
      (node (ref "U24") (pin "9") (pinfunction "A8_9") (pintype "input"))
    )
    (net (code "91") (name "/Hd_3(3.3)") (class "Default")
      (node (ref "U24") (pin "11") (pinfunction "Y8_11") (pintype "tri_state"))
      (node (ref "U5") (pin "125") (pinfunction "IO_L32N_1/GCLK5_125") (pintype "bidirectional"))
    )
    (net (code "96") (name "/INIT_B") (class "Default")
      (node (ref "R32") (pin "2") (pinfunction "2_2") (pintype "passive"))
      (node (ref "U27") (pin "8") (pinfunction "OE/~{RESET}_8") (pintype "bidirectional"))
      (node (ref "U5") (pin "58") (pinfunction "IO_L31N_4/INIT_B_58") (pintype "bidirectional"))
    )
    (net (code "97") (name "/IR_rec") (class "Default")
      (node (ref "C64") (pin "2") (pinfunction "2_2") (pintype "passive"))
      (node (ref "IR") (pin "3") (pinfunction "3_3") (pintype "passive"))
      (node (ref "R55") (pin "1") (pinfunction "1_1") (pintype "passive"))
      (node (ref "R93") (pin "2") (pinfunction "2_2") (pintype "passive"))
      (node (ref "U24") (pin "2") (pinfunction "A1_2") (pintype "input"))
    )
    (net (code "101") (name "/L_IO1") (class "Default")
      (node (ref "RS6") (pin "3") (pinfunction "3_3") (pintype "passive"))
      (node (ref "U5") (pin "1") (pinfunction "IO_L01P_7/VRN_7_1") (pintype "bidirectional"))
    )
    (net (code "102") (name "/L_IO2") (class "Default")
      (node (ref "RS6") (pin "1") (pinfunction "1_1") (pintype "passive"))
      (node (ref "U5") (pin "2") (pinfunction "IO_L01N_7/VRP_7_2") (pintype "bidirectional"))
    )
    (net (code "103") (name "/L_IO3") (class "Default")
      (node (ref "RS4") (pin "7") (pinfunction "7_7") (pintype "passive"))
      (node (ref "U5") (pin "4") (pinfunction "IO/VREF_7_4") (pintype "bidirectional"))
    )
    (net (code "104") (name "/L_IO4") (class "Default")
      (node (ref "RS4") (pin "5") (pinfunction "5_5") (pintype "passive"))
      (node (ref "U5") (pin "5") (pinfunction "IO_L20P_7_5") (pintype "bidirectional"))
    )
    (net (code "105") (name "/L_IO5") (class "Default")
      (node (ref "RS4") (pin "3") (pinfunction "3_3") (pintype "passive"))
      (node (ref "U5") (pin "6") (pinfunction "IO_L20N_7_6") (pintype "bidirectional"))
    )
    (net (code "106") (name "/L_IO6") (class "Default")
      (node (ref "RS4") (pin "1") (pinfunction "1_1") (pintype "passive"))
      (node (ref "U5") (pin "7") (pinfunction "IO_L21P_7_7") (pintype "bidirectional"))
    )
    (net (code "107") (name "/L_IO10") (class "Default")
      (node (ref "U2") (pin "14") (pinfunction "Y5_14") (pintype "tri_state"))
      (node (ref "U5") (pin "12") (pinfunction "IO_L23P_7_12") (pintype "bidirectional"))
    )
    (net (code "108") (name "/L_IO11") (class "Default")
      (node (ref "U2") (pin "13") (pinfunction "Y6_13") (pintype "tri_state"))
      (node (ref "U5") (pin "13") (pinfunction "IO_L23N_7_13") (pintype "bidirectional"))
    )
    (net (code "109") (name "/L_IO12") (class "Default")
      (node (ref "U2") (pin "12") (pinfunction "Y7_12") (pintype "tri_state"))
      (node (ref "U5") (pin "14") (pinfunction "IO_L24P_7_14") (pintype "bidirectional"))
    )
    (net (code "110") (name "/L_IO13") (class "Default")
      (node (ref "U2") (pin "11") (pinfunction "Y8_11") (pintype "tri_state"))
      (node (ref "U5") (pin "15") (pinfunction "IO_L24N_7_15") (pintype "bidirectional"))
    )
    (net (code "111") (name "/L_IO14") (class "Default")
      (node (ref "U1") (pin "18") (pinfunction "Y1_18") (pintype "tri_state"))
      (node (ref "U5") (pin "17") (pinfunction "IO_L40P_7_17") (pintype "bidirectional"))
    )
    (net (code "112") (name "/L_IO15") (class "Default")
      (node (ref "U1") (pin "17") (pinfunction "Y2_17") (pintype "tri_state"))
      (node (ref "U5") (pin "18") (pinfunction "IO_L40N_7/VREF_7_18") (pintype "bidirectional"))
    )
    (net (code "113") (name "/L_IO16") (class "Default")
      (node (ref "U1") (pin "16") (pinfunction "Y3_16") (pintype "tri_state"))
      (node (ref "U5") (pin "20") (pinfunction "IO_L40P_6/VREF_6_20") (pintype "bidirectional"))
    )
    (net (code "114") (name "/L_IO17") (class "Default")
      (node (ref "U1") (pin "15") (pinfunction "Y4_15") (pintype "tri_state"))
      (node (ref "U5") (pin "21") (pinfunction "IO_L40N_6_21") (pintype "bidirectional"))
    )
    (net (code "115") (name "/L_IO21") (class "Default")
      (node (ref "RS3") (pin "2") (pinfunction "2_2") (pintype "passive"))
      (node (ref "U5") (pin "26") (pinfunction "IO_L23N_6_26") (pintype "bidirectional"))
    )
    (net (code "116") (name "/L_IO22") (class "Default")
      (node (ref "RS3") (pin "4") (pinfunction "4_4") (pintype "passive"))
      (node (ref "U5") (pin "27") (pinfunction "IO_L22P_6_27") (pintype "bidirectional"))
    )
    (net (code "117") (name "/L_IO23") (class "Default")
      (node (ref "RS3") (pin "6") (pinfunction "6_6") (pintype "passive"))
      (node (ref "U5") (pin "28") (pinfunction "IO_L22N_6_28") (pintype "bidirectional"))
    )
    (net (code "118") (name "/L_IO24") (class "Default")
      (node (ref "RS3") (pin "8") (pinfunction "8_8") (pintype "passive"))
      (node (ref "U5") (pin "30") (pinfunction "IO_L21P_6_30") (pintype "bidirectional"))
    )
    (net (code "119") (name "/L_IO25") (class "Default")
      (node (ref "RS8") (pin "2") (pinfunction "2_2") (pintype "passive"))
      (node (ref "U5") (pin "31") (pinfunction "IO_L21N_6_31") (pintype "bidirectional"))
    )
    (net (code "120") (name "/L_IO26") (class "Default")
      (node (ref "RS8") (pin "4") (pinfunction "4_4") (pintype "passive"))
      (node (ref "U5") (pin "32") (pinfunction "IO_L20P_6_32") (pintype "bidirectional"))
    )
    (net (code "121") (name "/L_IO28") (class "Default")
      (node (ref "U5") (pin "35") (pinfunction "IO_L01P_6/VRN_6_35") (pintype "bidirectional"))
    )
    (net (code "122") (name "/L_IO29") (class "Default")
      (node (ref "U5") (pin "36") (pinfunction "IO_L01N_6/VRP_6_36") (pintype "bidirectional"))
    )
    (net (code "123") (name "/M1_1") (class "Default")
      (node (ref "RS19") (pin "5") (pinfunction "5_5") (pintype "passive"))
      (node (ref "RS2") (pin "6") (pinfunction "6_6") (pintype "passive"))
    )
    (net (code "124") (name "/M1_2") (class "Default")
      (node (ref "RS19") (pin "7") (pinfunction "7_7") (pintype "passive"))
      (node (ref "RS2") (pin "8") (pinfunction "8_8") (pintype "passive"))
    )
    (net (code "125") (name "/M1_3") (class "Default")
      (node (ref "RS19") (pin "1") (pinfunction "1_1") (pintype "passive"))
      (node (ref "RS2") (pin "2") (pinfunction "2_2") (pintype "passive"))
    )
    (net (code "126") (name "/M1_4") (class "Default")
      (node (ref "RS19") (pin "3") (pinfunction "3_3") (pintype "passive"))
      (node (ref "RS2") (pin "4") (pinfunction "4_4") (pintype "passive"))
    )
    (net (code "127") (name "/M1_5") (class "Default")
      (node (ref "RS15") (pin "3") (pinfunction "3_3") (pintype "passive"))
      (node (ref "RS5") (pin "6") (pinfunction "6_6") (pintype "passive"))
    )
    (net (code "128") (name "/M1_6") (class "Default")
      (node (ref "RS15") (pin "1") (pinfunction "1_1") (pintype "passive"))
      (node (ref "RS5") (pin "8") (pinfunction "8_8") (pintype "passive"))
    )
    (net (code "129") (name "/M2_1") (class "Default")
      (node (ref "RS14") (pin "7") (pinfunction "7_7") (pintype "passive"))
      (node (ref "RS6") (pin "2") (pinfunction "2_2") (pintype "passive"))
    )
    (net (code "130") (name "/M2_2") (class "Default")
      (node (ref "RS14") (pin "5") (pinfunction "5_5") (pintype "passive"))
      (node (ref "RS6") (pin "4") (pinfunction "4_4") (pintype "passive"))
    )
    (net (code "131") (name "/M2_3") (class "Default")
      (node (ref "RS21") (pin "4") (pinfunction "4_4") (pintype "passive"))
      (node (ref "RS4") (pin "6") (pinfunction "6_6") (pintype "passive"))
    )
    (net (code "132") (name "/M2_4") (class "Default")
      (node (ref "RS21") (pin "2") (pinfunction "2_2") (pintype "passive"))
      (node (ref "RS4") (pin "8") (pinfunction "8_8") (pintype "passive"))
    )
    (net (code "133") (name "/M2_5") (class "Default")
      (node (ref "RS21") (pin "8") (pinfunction "8_8") (pintype "passive"))
      (node (ref "RS4") (pin "2") (pinfunction "2_2") (pintype "passive"))
    )
    (net (code "134") (name "/M2_6") (class "Default")
      (node (ref "RS21") (pin "6") (pinfunction "6_6") (pintype "passive"))
      (node (ref "RS4") (pin "4") (pinfunction "4_4") (pintype "passive"))
    )
    (net (code "135") (name "/M3_1") (class "Default")
      (node (ref "RS18") (pin "1") (pinfunction "1_1") (pintype "passive"))
      (node (ref "RS3") (pin "7") (pinfunction "7_7") (pintype "passive"))
    )
    (net (code "136") (name "/M3_2") (class "Default")
      (node (ref "RS18") (pin "3") (pinfunction "3_3") (pintype "passive"))
      (node (ref "RS3") (pin "5") (pinfunction "5_5") (pintype "passive"))
    )
    (net (code "137") (name "/M3_3") (class "Default")
      (node (ref "RS13") (pin "5") (pinfunction "5_5") (pintype "passive"))
      (node (ref "RS8") (pin "3") (pinfunction "3_3") (pintype "passive"))
    )
    (net (code "138") (name "/M3_4") (class "Default")
      (node (ref "RS13") (pin "7") (pinfunction "7_7") (pintype "passive"))
      (node (ref "RS8") (pin "1") (pinfunction "1_1") (pintype "passive"))
    )
    (net (code "139") (name "/M3_5") (class "Default")
      (node (ref "RS18") (pin "5") (pinfunction "5_5") (pintype "passive"))
      (node (ref "RS3") (pin "3") (pinfunction "3_3") (pintype "passive"))
    )
    (net (code "140") (name "/M3_6") (class "Default")
      (node (ref "RS18") (pin "7") (pinfunction "7_7") (pintype "passive"))
      (node (ref "RS3") (pin "1") (pinfunction "1_1") (pintype "passive"))
    )
    (net (code "141") (name "/M4_1") (class "Default")
      (node (ref "RS11") (pin "2") (pinfunction "2_2") (pintype "passive"))
      (node (ref "RS20") (pin "4") (pinfunction "4_4") (pintype "passive"))
    )
    (net (code "142") (name "/M4_2") (class "Default")
      (node (ref "RS11") (pin "4") (pinfunction "4_4") (pintype "passive"))
      (node (ref "RS20") (pin "2") (pinfunction "2_2") (pintype "passive"))
    )
    (net (code "143") (name "/M4_3") (class "Default")
      (node (ref "RS16") (pin "4") (pinfunction "4_4") (pintype "passive"))
      (node (ref "RS9") (pin "6") (pinfunction "6_6") (pintype "passive"))
    )
    (net (code "144") (name "/M4_4") (class "Default")
      (node (ref "RS16") (pin "2") (pinfunction "2_2") (pintype "passive"))
      (node (ref "RS9") (pin "8") (pinfunction "8_8") (pintype "passive"))
    )
    (net (code "145") (name "/M4_5") (class "Default")
      (node (ref "RS16") (pin "8") (pinfunction "8_8") (pintype "passive"))
      (node (ref "RS9") (pin "2") (pinfunction "2_2") (pintype "passive"))
    )
    (net (code "146") (name "/M4_6") (class "Default")
      (node (ref "RS16") (pin "6") (pinfunction "6_6") (pintype "passive"))
      (node (ref "RS9") (pin "4") (pinfunction "4_4") (pintype "passive"))
    )
    (net (code "147") (name "/Md_1") (class "Default")
      (node (ref "RS12") (pin "5") (pinfunction "5_5") (pintype "passive"))
      (node (ref "RS7") (pin "3") (pinfunction "3_3") (pintype "passive"))
    )
    (net (code "148") (name "/Md_2") (class "Default")
      (node (ref "RS12") (pin "7") (pinfunction "7_7") (pintype "passive"))
      (node (ref "RS7") (pin "1") (pinfunction "1_1") (pintype "passive"))
    )
    (net (code "149") (name "/Md_3") (class "Default")
      (node (ref "RS12") (pin "1") (pinfunction "1_1") (pintype "passive"))
      (node (ref "RS7") (pin "7") (pinfunction "7_7") (pintype "passive"))
    )
    (net (code "150") (name "/Md_4") (class "Default")
      (node (ref "RS12") (pin "3") (pinfunction "3_3") (pintype "passive"))
      (node (ref "RS7") (pin "5") (pinfunction "5_5") (pintype "passive"))
    )
    (net (code "151") (name "/Md_5") (class "Default")
      (node (ref "RS17") (pin "8") (pinfunction "8_8") (pintype "passive"))
      (node (ref "RS6") (pin "6") (pinfunction "6_6") (pintype "passive"))
    )
    (net (code "152") (name "/Md_6") (class "Default")
      (node (ref "RS17") (pin "6") (pinfunction "6_6") (pintype "passive"))
      (node (ref "RS6") (pin "8") (pinfunction "8_8") (pintype "passive"))
    )
    (net (code "153") (name "/P.R TDO") (class "Default")
      (node (ref "R341") (pin "1") (pinfunction "1_1") (pintype "passive"))
      (node (ref "U27") (pin "17") (pinfunction "TDO_17") (pintype "output"))
    )
    (net (code "155") (name "/PROG_B") (class "Default")
      (node (ref "R33") (pin "1") (pinfunction "1_1") (pintype "passive"))
      (node (ref "U27") (pin "7") (pinfunction "~{CF}_7") (pintype "open_collector"))
      (node (ref "U5") (pin "143") (pinfunction "PROG_B_143") (pintype "input"))
    )
    (net (code "156") (name "/R_IO1") (class "Default")
      (node (ref "RS5") (pin "5") (pinfunction "5_5") (pintype "passive"))
      (node (ref "U5") (pin "108") (pinfunction "IO_L01N_2/VRP_2_108") (pintype "bidirectional"))
    )
    (net (code "157") (name "/R_IO2") (class "Default")
      (node (ref "RS5") (pin "7") (pinfunction "7_7") (pintype "passive"))
      (node (ref "U5") (pin "107") (pinfunction "IO_L01P_2/VRN_2_107") (pintype "bidirectional"))
    )
    (net (code "158") (name "/R_IO3") (class "Default")
      (node (ref "RS2") (pin "1") (pinfunction "1_1") (pintype "passive"))
      (node (ref "U5") (pin "105") (pinfunction "IO_L20N_2_105") (pintype "bidirectional"))
    )
    (net (code "159") (name "/R_IO4") (class "Default")
      (node (ref "RS2") (pin "3") (pinfunction "3_3") (pintype "passive"))
      (node (ref "U5") (pin "104") (pinfunction "IO_L20P_2_104") (pintype "bidirectional"))
    )
    (net (code "160") (name "/R_IO5") (class "Default")
      (node (ref "RS2") (pin "5") (pinfunction "5_5") (pintype "passive"))
      (node (ref "U5") (pin "103") (pinfunction "IO_L21N_2_103") (pintype "bidirectional"))
    )
    (net (code "161") (name "/R_IO6") (class "Default")
      (node (ref "RS2") (pin "7") (pinfunction "7_7") (pintype "passive"))
      (node (ref "U5") (pin "102") (pinfunction "IO_L21P_2_102") (pintype "bidirectional"))
    )
    (net (code "162") (name "/R_IO10") (class "Default")
      (node (ref "U3") (pin "15") (pinfunction "Y4_15") (pintype "tri_state"))
      (node (ref "U5") (pin "97") (pinfunction "IO_L23P_2_97") (pintype "bidirectional"))
    )
    (net (code "163") (name "/R_IO11") (class "Default")
      (node (ref "U3") (pin "16") (pinfunction "Y3_16") (pintype "tri_state"))
      (node (ref "U5") (pin "96") (pinfunction "IO_L24N_2_96") (pintype "bidirectional"))
    )
    (net (code "164") (name "/R_IO12") (class "Default")
      (node (ref "U3") (pin "17") (pinfunction "Y2_17") (pintype "tri_state"))
      (node (ref "U5") (pin "95") (pinfunction "IO_L24P_2_95") (pintype "bidirectional"))
    )
    (net (code "165") (name "/R_IO13") (class "Default")
      (node (ref "U3") (pin "18") (pinfunction "Y1_18") (pintype "tri_state"))
      (node (ref "U5") (pin "93") (pinfunction "IO_L40N_2_93") (pintype "bidirectional"))
    )
    (net (code "166") (name "/R_IO14") (class "Default")
      (node (ref "U4") (pin "11") (pinfunction "Y8_11") (pintype "tri_state"))
      (node (ref "U5") (pin "92") (pinfunction "IO_L40P_2/VREF_2_92") (pintype "bidirectional"))
    )
    (net (code "167") (name "/R_IO15") (class "Default")
      (node (ref "U4") (pin "12") (pinfunction "Y7_12") (pintype "tri_state"))
      (node (ref "U5") (pin "90") (pinfunction "IO_L40N_3/VREF_3_90") (pintype "bidirectional"))
    )
    (net (code "168") (name "/R_IO16") (class "Default")
      (node (ref "U4") (pin "13") (pinfunction "Y6_13") (pintype "tri_state"))
      (node (ref "U5") (pin "89") (pinfunction "IO_L40P_3_89") (pintype "bidirectional"))
    )
    (net (code "169") (name "/R_IO17") (class "Default")
      (node (ref "U4") (pin "14") (pinfunction "Y5_14") (pintype "tri_state"))
      (node (ref "U5") (pin "87") (pinfunction "IO_L24N_3_87") (pintype "bidirectional"))
    )
    (net (code "170") (name "/R_IO21") (class "Default")
      (node (ref "RS9") (pin "1") (pinfunction "1_1") (pintype "passive"))
      (node (ref "U5") (pin "83") (pinfunction "IO_L22N_3_83") (pintype "bidirectional"))
    )
    (net (code "171") (name "/R_IO22") (class "Default")
      (node (ref "RS9") (pin "3") (pinfunction "3_3") (pintype "passive"))
      (node (ref "U5") (pin "82") (pinfunction "IO_L22P_3_82") (pintype "bidirectional"))
    )
    (net (code "172") (name "/R_IO23") (class "Default")
      (node (ref "RS9") (pin "5") (pinfunction "5_5") (pintype "passive"))
      (node (ref "U5") (pin "80") (pinfunction "IO_L21N_3_80") (pintype "bidirectional"))
    )
    (net (code "173") (name "/R_IO24") (class "Default")
      (node (ref "RS9") (pin "7") (pinfunction "7_7") (pintype "passive"))
      (node (ref "U5") (pin "79") (pinfunction "IO_L21P_3_79") (pintype "bidirectional"))
    )
    (net (code "174") (name "/R_IO25") (class "Default")
      (node (ref "RS11") (pin "1") (pinfunction "1_1") (pintype "passive"))
      (node (ref "U5") (pin "78") (pinfunction "IO_L20N_3_78") (pintype "bidirectional"))
    )
    (net (code "175") (name "/R_IO26") (class "Default")
      (node (ref "RS11") (pin "3") (pinfunction "3_3") (pintype "passive"))
      (node (ref "U5") (pin "77") (pinfunction "IO_L20P_3_77") (pintype "bidirectional"))
    )
    (net (code "176") (name "/R_IO27") (class "Default")
      (node (ref "R25") (pin "1") (pinfunction "1_1") (pintype "passive"))
      (node (ref "U5") (pin "76") (pinfunction "IO_76") (pintype "bidirectional"))
    )
    (net (code "177") (name "/R_IO28") (class "Default")
      (node (ref "U5") (pin "74") (pinfunction "IO_L01N_3/VRP_3_74") (pintype "bidirectional"))
    )
    (net (code "178") (name "/R_IO29") (class "Default")
      (node (ref "U5") (pin "73") (pinfunction "IO_L01P_3/VRN_3_73") (pintype "bidirectional"))
    )
    (net (code "179") (name "/S_TDO") (class "Default")
      (node (ref "P13") (pin "4") (pinfunction "4_4") (pintype "passive"))
      (node (ref "U5") (pin "109") (pinfunction "TDO_109") (pintype "output"))
    )
    (net (code "180") (name "/Shoot_pulse") (class "Default")
      (node (ref "Booster") (pin "6") (pinfunction "6_6") (pintype "passive"))
      (node (ref "RS10") (pin "2") (pinfunction "2_2") (pintype "passive"))
      (node (ref "RS22") (pin "8") (pinfunction "8_8") (pintype "passive"))
    )
    (net (code "181") (name "/TCK") (class "Default")
      (node (ref "P13") (pin "3") (pinfunction "3_3") (pintype "passive"))
      (node (ref "R342") (pin "1") (pinfunction "1_1") (pintype "passive"))
      (node (ref "U27") (pin "6") (pinfunction "TCK_6") (pintype "input"))
    )
    (net (code "182") (name "/TDI") (class "Default")
      (node (ref "P13") (pin "5") (pinfunction "5_5") (pintype "passive"))
      (node (ref "U27") (pin "4") (pinfunction "TDI_4") (pintype "input"))
    )
    (net (code "183") (name "/TMS") (class "Default")
      (node (ref "P13") (pin "6") (pinfunction "6_6") (pintype "passive"))
      (node (ref "R343") (pin "1") (pinfunction "1_1") (pintype "passive"))
      (node (ref "U27") (pin "5") (pinfunction "TMS_5") (pintype "input"))
    )
    (net (code "184") (name "/U_IO1") (class "Default")
      (node (ref "RS6") (pin "5") (pinfunction "5_5") (pintype "passive"))
      (node (ref "U5") (pin "141") (pinfunction "IO_L01N_0/VRP_0_141") (pintype "bidirectional"))
    )
    (net (code "185") (name "/U_IO2") (class "Default")
      (node (ref "RS6") (pin "7") (pinfunction "7_7") (pintype "passive"))
      (node (ref "U5") (pin "140") (pinfunction "IO_L01P_0/VRN_0_140") (pintype "bidirectional"))
    )
    (net (code "186") (name "/U_IO3") (class "Default")
      (node (ref "RS7") (pin "8") (pinfunction "8_8") (pintype "passive"))
      (node (ref "U5") (pin "137") (pinfunction "IO_L27N_0_137") (pintype "bidirectional"))
    )
    (net (code "187") (name "/U_IO4") (class "Default")
      (node (ref "RS7") (pin "6") (pinfunction "6_6") (pintype "passive"))
      (node (ref "U5") (pin "135") (pinfunction "IO_L27P_0_135") (pintype "bidirectional"))
    )
    (net (code "188") (name "/U_IO5") (class "Default")
      (node (ref "RS7") (pin "4") (pinfunction "4_4") (pintype "passive"))
      (node (ref "U5") (pin "132") (pinfunction "IO_L30N_0_132") (pintype "bidirectional"))
    )
    (net (code "189") (name "/U_IO6") (class "Default")
      (node (ref "RS7") (pin "2") (pinfunction "2_2") (pintype "passive"))
      (node (ref "U5") (pin "131") (pinfunction "IO_L30P_0_131") (pintype "bidirectional"))
    )
    (net (code "190") (name "/U_IO9") (class "Default")
      (node (ref "U24") (pin "17") (pinfunction "Y2_17") (pintype "tri_state"))
      (node (ref "U5") (pin "122") (pinfunction "IO_L31P_1_122") (pintype "bidirectional"))
    )
    (net (code "191") (name "/U_IO10") (class "Default")
      (node (ref "U24") (pin "18") (pinfunction "Y1_18") (pintype "tri_state"))
      (node (ref "U5") (pin "119") (pinfunction "IO_L28N_1_119") (pintype "bidirectional"))
    )
    (net (code "192") (name "/U_IO11") (class "Default")
      (node (ref "R333") (pin "2") (pinfunction "2_2") (pintype "passive"))
      (node (ref "U5") (pin "118") (pinfunction "IO_L28P_1_118") (pintype "bidirectional"))
    )
    (net (code "193") (name "/U_IO12") (class "Default")
      (node (ref "RS22") (pin "3") (pinfunction "3_3") (pintype "passive"))
      (node (ref "U5") (pin "116") (pinfunction "IO_116") (pintype "bidirectional"))
    )
    (net (code "194") (name "/U_IO13") (class "Default")
      (node (ref "RS22") (pin "5") (pinfunction "5_5") (pintype "passive"))
      (node (ref "U5") (pin "113") (pinfunction "IO_L01N_1/VRP_1_113") (pintype "bidirectional"))
    )
    (net (code "195") (name "/U_IO14") (class "Default")
      (node (ref "RS22") (pin "7") (pinfunction "7_7") (pintype "passive"))
      (node (ref "U5") (pin "112") (pinfunction "IO_L01P_1/VRN_1_112") (pintype "bidirectional"))
    )
    (net (code "196") (name "/booster_ready") (class "Default")
      (node (ref "Booster") (pin "3") (pinfunction "3_3") (pintype "passive"))
      (node (ref "RS10") (pin "8") (pinfunction "8_8") (pintype "passive"))
      (node (ref "U24") (pin "3") (pinfunction "A2_3") (pintype "input"))
    )
    (net (code "206") (name "GND") (class "Default")
      (node (ref "C1") (pin "2") (pinfunction "2_2") (pintype "passive"))
      (node (ref "C11") (pin "1") (pinfunction "1_1") (pintype "passive"))
      (node (ref "C110") (pin "2") (pinfunction "2_2") (pintype "passive"))
      (node (ref "C12") (pin "1") (pinfunction "1_1") (pintype "passive"))
      (node (ref "C120") (pin "2") (pinfunction "2_2") (pintype "passive"))
      (node (ref "C13") (pin "1") (pinfunction "1_1") (pintype "passive"))
      (node (ref "C130") (pin "2") (pinfunction "2_2") (pintype "passive"))
      (node (ref "C14") (pin "1") (pinfunction "1_1") (pintype "passive"))
      (node (ref "C15") (pin "1") (pinfunction "1_1") (pintype "passive"))
      (node (ref "C16") (pin "1") (pinfunction "1_1") (pintype "passive"))
      (node (ref "C17") (pin "1") (pinfunction "1_1") (pintype "passive"))
      (node (ref "C18") (pin "1") (pinfunction "1_1") (pintype "passive"))
      (node (ref "C2") (pin "2") (pinfunction "2_2") (pintype "passive"))
      (node (ref "C21") (pin "2") (pinfunction "2_2") (pintype "passive"))
      (node (ref "C23") (pin "1") (pinfunction "1_1") (pintype "passive"))
      (node (ref "C24") (pin "1") (pinfunction "1_1") (pintype "passive"))
      (node (ref "C25") (pin "1") (pinfunction "1_1") (pintype "passive"))
      (node (ref "C3") (pin "2") (pinfunction "2_2") (pintype "passive"))
      (node (ref "C33") (pin "1") (pinfunction "1_1") (pintype "passive"))
      (node (ref "C34") (pin "1") (pinfunction "1_1") (pintype "passive"))
      (node (ref "C35") (pin "1") (pinfunction "1_1") (pintype "passive"))
      (node (ref "C36") (pin "1") (pinfunction "1_1") (pintype "passive"))
      (node (ref "C37") (pin "1") (pinfunction "1_1") (pintype "passive"))
      (node (ref "C38") (pin "1") (pinfunction "1_1") (pintype "passive"))
      (node (ref "C39") (pin "1") (pinfunction "1_1") (pintype "passive"))
      (node (ref "C5") (pin "2") (pinfunction "2_2") (pintype "passive"))
      (node (ref "C6") (pin "2") (pinfunction "2_2") (pintype "passive"))
      (node (ref "C63") (pin "2") (pinfunction "2_2") (pintype "passive"))
      (node (ref "C64") (pin "1") (pinfunction "1_1") (pintype "passive"))
      (node (ref "C65") (pin "2") (pinfunction "2_2") (pintype "passive"))
      (node (ref "C7") (pin "2") (pinfunction "2_2") (pintype "passive"))
      (node (ref "C72") (pin "2") (pinfunction "2_2") (pintype "passive"))
      (node (ref "C73") (pin "1") (pinfunction "1_1") (pintype "passive"))
      (node (ref "C74") (pin "1") (pinfunction "1_1") (pintype "passive"))
      (node (ref "C75") (pin "1") (pinfunction "1_1") (pintype "passive"))
      (node (ref "C76") (pin "1") (pinfunction "1_1") (pintype "passive"))
      (node (ref "C77") (pin "1") (pinfunction "1_1") (pintype "passive"))
      (node (ref "C78") (pin "1") (pinfunction "1_1") (pintype "passive"))
      (node (ref "C79") (pin "1") (pinfunction "1_1") (pintype "passive"))
      (node (ref "C80") (pin "2") (pinfunction "2_2") (pintype "passive"))
      (node (ref "C9") (pin "2") (pinfunction "2_2") (pintype "passive"))
      (node (ref "C_IR") (pin "2") (pinfunction "2_2") (pintype "passive"))
      (node (ref "D4") (pin "2") (pinfunction "K_2") (pintype "passive"))
      (node (ref "IR") (pin "4") (pinfunction "4_4") (pintype "passive"))
      (node (ref "P13") (pin "2") (pinfunction "2_2") (pintype "passive"))
      (node (ref "P91") (pin "4") (pinfunction "4_4") (pintype "passive"))
      (node (ref "P91") (pin "SHD") (pinfunction "SHD_SHD") (pintype "passive"))
      (node (ref "P92") (pin "4") (pinfunction "4_4") (pintype "passive"))
      (node (ref "P92") (pin "SHD") (pinfunction "SHD_SHD") (pintype "passive"))
      (node (ref "P93") (pin "4") (pinfunction "4_4") (pintype "passive"))
      (node (ref "P93") (pin "SHD") (pinfunction "SHD_SHD") (pintype "passive"))
      (node (ref "P94") (pin "4") (pinfunction "4_4") (pintype "passive"))
      (node (ref "P94") (pin "SHD") (pinfunction "SHD_SHD") (pintype "passive"))
      (node (ref "R122") (pin "1") (pinfunction "1_1") (pintype "passive"))
      (node (ref "R22") (pin "2") (pinfunction "2_2") (pintype "passive"))
      (node (ref "R27") (pin "2") (pinfunction "2_2") (pintype "passive"))
      (node (ref "R346") (pin "1") (pinfunction "1_1") (pintype "passive"))
      (node (ref "R93") (pin "1") (pinfunction "1_1") (pintype "passive"))
      (node (ref "RS12") (pin "2") (pinfunction "2_2") (pintype "passive"))
      (node (ref "RS12") (pin "4") (pinfunction "4_4") (pintype "passive"))
      (node (ref "RS12") (pin "6") (pinfunction "6_6") (pintype "passive"))
      (node (ref "RS12") (pin "8") (pinfunction "8_8") (pintype "passive"))
      (node (ref "RS13") (pin "2") (pinfunction "2_2") (pintype "passive"))
      (node (ref "RS13") (pin "4") (pinfunction "4_4") (pintype "passive"))
      (node (ref "RS13") (pin "6") (pinfunction "6_6") (pintype "passive"))
      (node (ref "RS13") (pin "8") (pinfunction "8_8") (pintype "passive"))
      (node (ref "RS14") (pin "2") (pinfunction "2_2") (pintype "passive"))
      (node (ref "RS14") (pin "4") (pinfunction "4_4") (pintype "passive"))
      (node (ref "RS14") (pin "6") (pinfunction "6_6") (pintype "passive"))
      (node (ref "RS14") (pin "8") (pinfunction "8_8") (pintype "passive"))
      (node (ref "RS15") (pin "2") (pinfunction "2_2") (pintype "passive"))
      (node (ref "RS15") (pin "4") (pinfunction "4_4") (pintype "passive"))
      (node (ref "RS15") (pin "6") (pinfunction "6_6") (pintype "passive"))
      (node (ref "RS15") (pin "8") (pinfunction "8_8") (pintype "passive"))
      (node (ref "RS16") (pin "1") (pinfunction "1_1") (pintype "passive"))
      (node (ref "RS16") (pin "3") (pinfunction "3_3") (pintype "passive"))
      (node (ref "RS16") (pin "5") (pinfunction "5_5") (pintype "passive"))
      (node (ref "RS16") (pin "7") (pinfunction "7_7") (pintype "passive"))
      (node (ref "RS17") (pin "1") (pinfunction "1_1") (pintype "passive"))
      (node (ref "RS17") (pin "3") (pinfunction "3_3") (pintype "passive"))
      (node (ref "RS17") (pin "5") (pinfunction "5_5") (pintype "passive"))
      (node (ref "RS17") (pin "7") (pinfunction "7_7") (pintype "passive"))
      (node (ref "RS18") (pin "2") (pinfunction "2_2") (pintype "passive"))
      (node (ref "RS18") (pin "4") (pinfunction "4_4") (pintype "passive"))
      (node (ref "RS18") (pin "6") (pinfunction "6_6") (pintype "passive"))
      (node (ref "RS18") (pin "8") (pinfunction "8_8") (pintype "passive"))
      (node (ref "RS19") (pin "2") (pinfunction "2_2") (pintype "passive"))
      (node (ref "RS19") (pin "4") (pinfunction "4_4") (pintype "passive"))
      (node (ref "RS19") (pin "6") (pinfunction "6_6") (pintype "passive"))
      (node (ref "RS19") (pin "8") (pinfunction "8_8") (pintype "passive"))
      (node (ref "RS20") (pin "1") (pinfunction "1_1") (pintype "passive"))
      (node (ref "RS20") (pin "3") (pinfunction "3_3") (pintype "passive"))
      (node (ref "RS20") (pin "5") (pinfunction "5_5") (pintype "passive"))
      (node (ref "RS20") (pin "7") (pinfunction "7_7") (pintype "passive"))
      (node (ref "RS21") (pin "1") (pinfunction "1_1") (pintype "passive"))
      (node (ref "RS21") (pin "3") (pinfunction "3_3") (pintype "passive"))
      (node (ref "RS21") (pin "5") (pinfunction "5_5") (pintype "passive"))
      (node (ref "RS21") (pin "7") (pinfunction "7_7") (pintype "passive"))
      (node (ref "RST_CAP_1") (pin "1") (pinfunction "1_1") (pintype "passive"))
      (node (ref "R_done_led") (pin "1") (pinfunction "1_1") (pintype "passive"))
      (node (ref "U1") (pin "1") (pinfunction "~{OE}1_1") (pintype "input"))
      (node (ref "U1") (pin "10") (pinfunction "GND_10") (pintype "power_in"))
      (node (ref "U1") (pin "19") (pinfunction "~{OE}2_19") (pintype "input"))
      (node (ref "U2") (pin "1") (pinfunction "~{OE}1_1") (pintype "input"))
      (node (ref "U2") (pin "10") (pinfunction "GND_10") (pintype "power_in"))
      (node (ref "U2") (pin "19") (pinfunction "~{OE}2_19") (pintype "input"))
      (node (ref "U22") (pin "3") (pinfunction "GND_3") (pintype "power_in"))
      (node (ref "U24") (pin "1") (pinfunction "~{OE}1_1") (pintype "input"))
      (node (ref "U24") (pin "10") (pinfunction "GND_10") (pintype "power_in"))
      (node (ref "U24") (pin "19") (pinfunction "~{OE}2_19") (pintype "input"))
      (node (ref "U27") (pin "11") (pinfunction "GND_11") (pintype "power_in"))
      (node (ref "U3") (pin "1") (pinfunction "~{OE}1_1") (pintype "input"))
      (node (ref "U3") (pin "10") (pinfunction "GND_10") (pintype "power_in"))
      (node (ref "U3") (pin "19") (pinfunction "~{OE}2_19") (pintype "input"))
      (node (ref "U4") (pin "1") (pinfunction "~{OE}1_1") (pintype "input"))
      (node (ref "U4") (pin "10") (pinfunction "GND_10") (pintype "power_in"))
      (node (ref "U4") (pin "19") (pinfunction "~{OE}2_19") (pintype "input"))
      (node (ref "U5") (pin "101") (pinfunction "GND_101") (pintype "power_in"))
      (node (ref "U5") (pin "114") (pinfunction "GND_114") (pintype "power_in"))
      (node (ref "U5") (pin "117") (pinfunction "GND_117") (pintype "power_in"))
      (node (ref "U5") (pin "136") (pinfunction "GND_136") (pintype "power_in"))
      (node (ref "U5") (pin "139") (pinfunction "GND_139") (pintype "power_in"))
      (node (ref "U5") (pin "16") (pinfunction "GND_16") (pintype "power_in"))
      (node (ref "U5") (pin "22") (pinfunction "GND_22") (pintype "power_in"))
      (node (ref "U5") (pin "29") (pinfunction "GND_29") (pintype "power_in"))
      (node (ref "U5") (pin "37") (pinfunction "M1_37") (pintype "input"))
      (node (ref "U5") (pin "38") (pinfunction "M0_38") (pintype "input"))
      (node (ref "U5") (pin "39") (pinfunction "M2_39") (pintype "input"))
      (node (ref "U5") (pin "42") (pinfunction "GND_42") (pintype "power_in"))
      (node (ref "U5") (pin "45") (pinfunction "GND_45") (pintype "power_in"))
      (node (ref "U5") (pin "64") (pinfunction "GND_64") (pintype "power_in"))
      (node (ref "U5") (pin "67") (pinfunction "GND_67") (pintype "power_in"))
      (node (ref "U5") (pin "81") (pinfunction "GND_81") (pintype "power_in"))
      (node (ref "U5") (pin "88") (pinfunction "GND_88") (pintype "power_in"))
      (node (ref "U5") (pin "9") (pinfunction "GND_9") (pintype "power_in"))
      (node (ref "U5") (pin "94") (pinfunction "GND_94") (pintype "power_in"))
      (node (ref "X1") (pin "2") (pinfunction "GND_2") (pintype "power_in"))
    )
    (net (code "207") (name "Net-(Booster-Pad1)") (class "Default")
      (node (ref "Booster") (pin "1") (pinfunction "1_1") (pintype "passive"))
      (node (ref "R26") (pin "2") (pinfunction "2_2") (pintype "passive"))
    )
    (net (code "208") (name "Net-(C94-Pad1)") (class "Default")
      (node (ref "C94") (pin "1") (pinfunction "1_1") (pintype "passive"))
      (node (ref "R10") (pin "2") (pinfunction "2_2") (pintype "passive"))
    )
    (net (code "209") (name "Net-(C95-Pad1)") (class "Default")
      (node (ref "C95") (pin "1") (pinfunction "1_1") (pintype "passive"))
      (node (ref "R11") (pin "2") (pinfunction "2_2") (pintype "passive"))
    )
    (net (code "210") (name "Net-(C96-Pad1)") (class "Default")
      (node (ref "C96") (pin "1") (pinfunction "1_1") (pintype "passive"))
      (node (ref "R12") (pin "2") (pinfunction "2_2") (pintype "passive"))
    )
    (net (code "211") (name "Net-(C97-Pad1)") (class "Default")
      (node (ref "C97") (pin "1") (pinfunction "1_1") (pintype "passive"))
      (node (ref "R13") (pin "2") (pinfunction "2_2") (pintype "passive"))
    )
    (net (code "212") (name "Net-(C98-Pad1)") (class "Default")
      (node (ref "C98") (pin "1") (pinfunction "1_1") (pintype "passive"))
      (node (ref "R14") (pin "2") (pinfunction "2_2") (pintype "passive"))
    )
    (net (code "213") (name "Net-(C99-Pad1)") (class "Default")
      (node (ref "C99") (pin "1") (pinfunction "1_1") (pintype "passive"))
      (node (ref "R15") (pin "2") (pinfunction "2_2") (pintype "passive"))
    )
    (net (code "214") (name "Net-(C100-Pad1)") (class "Default")
      (node (ref "C100") (pin "1") (pinfunction "1_1") (pintype "passive"))
      (node (ref "R16") (pin "2") (pinfunction "2_2") (pintype "passive"))
    )
    (net (code "215") (name "Net-(C101-Pad1)") (class "Default")
      (node (ref "C101") (pin "1") (pinfunction "1_1") (pintype "passive"))
      (node (ref "R17") (pin "2") (pinfunction "2_2") (pintype "passive"))
    )
    (net (code "216") (name "Net-(D4-A)") (class "Default")
      (node (ref "D4") (pin "1") (pinfunction "A_1") (pintype "passive"))
      (node (ref "R25") (pin "2") (pinfunction "2_2") (pintype "passive"))
    )
    (net (code "217") (name "Net-(D_Done-A)") (class "Default")
      (node (ref "D_Done") (pin "1") (pinfunction "A_1") (pintype "passive"))
      (node (ref "U24") (pin "16") (pinfunction "Y3_16") (pintype "tri_state"))
    )
    (net (code "218") (name "Net-(D_Done-K)") (class "Default")
      (node (ref "D_Done") (pin "2") (pinfunction "K_2") (pintype "passive"))
      (node (ref "R_done_led") (pin "2") (pinfunction "2_2") (pintype "passive"))
    )
    (net (code "219") (name "Net-(IR-Pad1)") (class "Default")
      (node (ref "IR") (pin "1") (pinfunction "1_1") (pintype "passive"))
      (node (ref "R44") (pin "1") (pinfunction "1_1") (pintype "passive"))
    )
    (net (code "220") (name "Net-(IR-Pad2)") (class "Default")
      (node (ref "IR") (pin "2") (pinfunction "2_2") (pintype "passive"))
      (node (ref "R18") (pin "2") (pinfunction "2_2") (pintype "passive"))
    )
    (net (code "221") (name "Net-(R31-Pad2)") (class "Default")
      (node (ref "R31") (pin "2") (pinfunction "2_2") (pintype "passive"))
      (node (ref "R345") (pin "2") (pinfunction "2_2") (pintype "passive"))
      (node (ref "R346") (pin "2") (pinfunction "2_2") (pintype "passive"))
    )
    (net (code "222") (name "Net-(R122-Pad2)") (class "Default")
      (node (ref "R122") (pin "2") (pinfunction "2_2") (pintype "passive"))
      (node (ref "S4") (pin "1") (pinfunction "1_1") (pintype "passive"))
    )
    (net (code "223") (name "Net-(U5I-TCK)") (class "Default")
      (node (ref "R342") (pin "2") (pinfunction "2_2") (pintype "passive"))
      (node (ref "U5") (pin "110") (pinfunction "TCK_110") (pintype "input"))
    )
    (net (code "224") (name "Net-(U5I-TDI)") (class "Default")
      (node (ref "R341") (pin "2") (pinfunction "2_2") (pintype "passive"))
      (node (ref "U5") (pin "144") (pinfunction "TDI_144") (pintype "input"))
    )
    (net (code "225") (name "Net-(U5I-TMS)") (class "Default")
      (node (ref "R343") (pin "2") (pinfunction "2_2") (pintype "passive"))
      (node (ref "U5") (pin "111") (pinfunction "TMS_111") (pintype "input"))
    )
    (net (code "226") (name "Net-(U22-INA)") (class "Default")
      (node (ref "R333") (pin "1") (pinfunction "1_1") (pintype "passive"))
      (node (ref "U22") (pin "2") (pinfunction "INA_2") (pintype "input"))
    )
    (net (code "227") (name "Net-(U22-INB)") (class "Default")
      (node (ref "R22") (pin "1") (pinfunction "1_1") (pintype "passive"))
      (node (ref "U22") (pin "4") (pinfunction "INB_4") (pintype "input"))
    )
    (net (code "228") (name "Net-(U22-OUTA)") (class "Default")
      (node (ref "R18") (pin "1") (pinfunction "1_1") (pintype "passive"))
      (node (ref "U22") (pin "7") (pinfunction "OUTA_7") (pintype "output"))
    )
    (net (code "229") (name "V 1.2") (class "Default")
      (node (ref "C33") (pin "2") (pinfunction "2_2") (pintype "passive"))
      (node (ref "C34") (pin "2") (pinfunction "2_2") (pintype "passive"))
      (node (ref "C35") (pin "2") (pinfunction "2_2") (pintype "passive"))
      (node (ref "C36") (pin "2") (pinfunction "2_2") (pintype "passive"))
      (node (ref "C75") (pin "2") (pinfunction "2_2") (pintype "passive"))
      (node (ref "U5") (pin "121") (pinfunction "VCCINT_121") (pintype "power_in"))
      (node (ref "U5") (pin "133") (pinfunction "VCCINT_133") (pintype "power_in"))
      (node (ref "U5") (pin "49") (pinfunction "VCCINT_49") (pintype "power_in"))
      (node (ref "U5") (pin "61") (pinfunction "VCCINT_61") (pintype "power_in"))
    )
    (net (code "230") (name "V 2.5") (class "Default")
      (node (ref "C11") (pin "2") (pinfunction "2_2") (pintype "passive"))
      (node (ref "C12") (pin "2") (pinfunction "2_2") (pintype "passive"))
      (node (ref "C13") (pin "2") (pinfunction "2_2") (pintype "passive"))
      (node (ref "C73") (pin "2") (pinfunction "2_2") (pintype "passive"))
      (node (ref "C74") (pin "2") (pinfunction "2_2") (pintype "passive"))
      (node (ref "R33") (pin "2") (pinfunction "2_2") (pintype "passive"))
      (node (ref "R34") (pin "1") (pinfunction "1_1") (pintype "passive"))
      (node (ref "U5") (pin "120") (pinfunction "VCCAUX_120") (pintype "power_in"))
      (node (ref "U5") (pin "134") (pinfunction "VCCAUX_134") (pintype "power_in"))
      (node (ref "U5") (pin "48") (pinfunction "VCCAUX_48") (pintype "power_in"))
      (node (ref "U5") (pin "62") (pinfunction "VCCAUX_62") (pintype "power_in"))
    )
    (net (code "231") (name "V 3.3") (class "Default")
      (node (ref "Booster") (pin "2") (pinfunction "2_2") (pintype "passive"))
      (node (ref "C14") (pin "2") (pinfunction "2_2") (pintype "passive"))
      (node (ref "C15") (pin "2") (pinfunction "2_2") (pintype "passive"))
      (node (ref "C16") (pin "2") (pinfunction "2_2") (pintype "passive"))
      (node (ref "C17") (pin "2") (pinfunction "2_2") (pintype "passive"))
      (node (ref "C18") (pin "2") (pinfunction "2_2") (pintype "passive"))
      (node (ref "C21") (pin "1") (pinfunction "1_1") (pintype "passive"))
      (node (ref "C23") (pin "2") (pinfunction "2_2") (pintype "passive"))
      (node (ref "C24") (pin "2") (pinfunction "2_2") (pintype "passive"))
      (node (ref "C25") (pin "2") (pinfunction "2_2") (pintype "passive"))
      (node (ref "C37") (pin "2") (pinfunction "2_2") (pintype "passive"))
      (node (ref "C38") (pin "2") (pinfunction "2_2") (pintype "passive"))
      (node (ref "C39") (pin "2") (pinfunction "2_2") (pintype "passive"))
      (node (ref "C72") (pin "1") (pinfunction "1_1") (pintype "passive"))
      (node (ref "C76") (pin "2") (pinfunction "2_2") (pintype "passive"))
      (node (ref "C77") (pin "2") (pinfunction "2_2") (pintype "passive"))
      (node (ref "C78") (pin "2") (pinfunction "2_2") (pintype "passive"))
      (node (ref "C79") (pin "2") (pinfunction "2_2") (pintype "passive"))
      (node (ref "C80") (pin "1") (pinfunction "1_1") (pintype "passive"))
      (node (ref "P13") (pin "1") (pinfunction "1_1") (pintype "passive"))
      (node (ref "R(rst)") (pin "1") (pinfunction "1_1") (pintype "passive"))
      (node (ref "R32") (pin "1") (pinfunction "1_1") (pintype "passive"))
      (node (ref "R345") (pin "1") (pinfunction "1_1") (pintype "passive"))
      (node (ref "R55") (pin "2") (pinfunction "2_2") (pintype "passive"))
      (node (ref "RS10") (pin "1") (pinfunction "1_1") (pintype "passive"))
      (node (ref "RS10") (pin "3") (pinfunction "3_3") (pintype "passive"))
      (node (ref "RS10") (pin "5") (pinfunction "5_5") (pintype "passive"))
      (node (ref "RS10") (pin "7") (pinfunction "7_7") (pintype "passive"))
      (node (ref "U1") (pin "20") (pinfunction "VCC_20") (pintype "power_in"))
      (node (ref "U2") (pin "20") (pinfunction "VCC_20") (pintype "power_in"))
      (node (ref "U24") (pin "20") (pinfunction "VCC_20") (pintype "power_in"))
      (node (ref "U27") (pin "18") (pinfunction "VCCINT_18") (pintype "power_in"))
      (node (ref "U27") (pin "19") (pinfunction "VCCO_19") (pintype "power_in"))
      (node (ref "U27") (pin "20") (pinfunction "VCCJ_20") (pintype "power_in"))
      (node (ref "U3") (pin "20") (pinfunction "VCC_20") (pintype "power_in"))
      (node (ref "U4") (pin "20") (pinfunction "VCC_20") (pintype "power_in"))
      (node (ref "U5") (pin "106") (pinfunction "VCCO_RIGHT_106") (pintype "power_in"))
      (node (ref "U5") (pin "115") (pinfunction "VCCO_TOP_115") (pintype "power_in"))
      (node (ref "U5") (pin "126") (pinfunction "VCCO_TOP_126") (pintype "power_in"))
      (node (ref "U5") (pin "138") (pinfunction "VCCO_TOP_138") (pintype "power_in"))
      (node (ref "U5") (pin "19") (pinfunction "VCCO_LEFT_19") (pintype "power_in"))
      (node (ref "U5") (pin "3") (pinfunction "VCCO_LEFT_3") (pintype "power_in"))
      (node (ref "U5") (pin "34") (pinfunction "VCCO_LEFT_34") (pintype "power_in"))
      (node (ref "U5") (pin "43") (pinfunction "VCCO_BOTTOM_43") (pintype "power_in"))
      (node (ref "U5") (pin "54") (pinfunction "VCCO_BOTTOM_54") (pintype "power_in"))
      (node (ref "U5") (pin "66") (pinfunction "VCCO_BOTTOM_66") (pintype "power_in"))
      (node (ref "U5") (pin "75") (pinfunction "VCCO_RIGHT_75") (pintype "power_in"))
      (node (ref "U5") (pin "91") (pinfunction "VCCO_RIGHT_91") (pintype "power_in"))
      (node (ref "X1") (pin "4") (pinfunction "VDD_4") (pintype "power_in"))
    )
    (net (code "232") (name "V 12") (class "Default")
      (node (ref "C_IR") (pin "1") (pinfunction "1_1") (pintype "passive"))
      (node (ref "R44") (pin "2") (pinfunction "2_2") (pintype "passive"))
      (node (ref "U22") (pin "6") (pinfunction "VDD_6") (pintype "power_in"))
    )
    (net (code "233") (name "VCC") (class "Default")
      (node (ref "C1") (pin "1") (pinfunction "1_1") (pintype "passive"))
      (node (ref "C110") (pin "1") (pinfunction "1_1") (pintype "passive"))
      (node (ref "C120") (pin "1") (pinfunction "1_1") (pintype "passive"))
      (node (ref "C130") (pin "1") (pinfunction "1_1") (pintype "passive"))
      (node (ref "C2") (pin "1") (pinfunction "1_1") (pintype "passive"))
      (node (ref "C3") (pin "1") (pinfunction "1_1") (pintype "passive"))
      (node (ref "C5") (pin "1") (pinfunction "1_1") (pintype "passive"))
      (node (ref "C6") (pin "1") (pinfunction "1_1") (pintype "passive"))
      (node (ref "C63") (pin "1") (pinfunction "1_1") (pintype "passive"))
      (node (ref "C65") (pin "1") (pinfunction "1_1") (pintype "passive"))
      (node (ref "C7") (pin "1") (pinfunction "1_1") (pintype "passive"))
      (node (ref "C9") (pin "1") (pinfunction "1_1") (pintype "passive"))
      (node (ref "P91") (pin "1") (pinfunction "1_1") (pintype "passive"))
      (node (ref "P92") (pin "1") (pinfunction "1_1") (pintype "passive"))
      (node (ref "P93") (pin "1") (pinfunction "1_1") (pintype "passive"))
      (node (ref "P94") (pin "1") (pinfunction "1_1") (pintype "passive"))
    )
    (net (code "234") (name "unconnected-(RS5-Pad1)") (class "Default")
      (node (ref "RS5") (pin "1") (pinfunction "1_1") (pintype "passive"))
    )
    (net (code "235") (name "unconnected-(RS5-Pad2)") (class "Default")
      (node (ref "RS5") (pin "2") (pinfunction "2_2") (pintype "passive"))
    )
    (net (code "236") (name "unconnected-(RS5-Pad3)") (class "Default")
      (node (ref "RS5") (pin "3") (pinfunction "3_3") (pintype "passive"))
    )
    (net (code "237") (name "unconnected-(RS5-Pad4)") (class "Default")
      (node (ref "RS5") (pin "4") (pinfunction "4_4") (pintype "passive"))
    )
    (net (code "238") (name "unconnected-(RS8-Pad5)") (class "Default")
      (node (ref "RS8") (pin "5") (pinfunction "5_5") (pintype "passive"))
    )
    (net (code "239") (name "unconnected-(RS8-Pad6)") (class "Default")
      (node (ref "RS8") (pin "6") (pinfunction "6_6") (pintype "passive"))
    )
    (net (code "240") (name "unconnected-(RS8-Pad7)") (class "Default")
      (node (ref "RS8") (pin "7") (pinfunction "7_7") (pintype "passive"))
    )
    (net (code "241") (name "unconnected-(RS8-Pad8)") (class "Default")
      (node (ref "RS8") (pin "8") (pinfunction "8_8") (pintype "passive"))
    )
    (net (code "242") (name "unconnected-(RS11-Pad5)") (class "Default")
      (node (ref "RS11") (pin "5") (pinfunction "5_5") (pintype "passive"))
    )
    (net (code "243") (name "unconnected-(RS11-Pad6)") (class "Default")
      (node (ref "RS11") (pin "6") (pinfunction "6_6") (pintype "passive"))
    )
    (net (code "244") (name "unconnected-(RS11-Pad7)") (class "Default")
      (node (ref "RS11") (pin "7") (pinfunction "7_7") (pintype "passive"))
    )
    (net (code "245") (name "unconnected-(RS11-Pad8)") (class "Default")
      (node (ref "RS11") (pin "8") (pinfunction "8_8") (pintype "passive"))
    )
    (net (code "246") (name "unconnected-(RS13-Pad1)") (class "Default")
      (node (ref "RS13") (pin "1") (pinfunction "1_1") (pintype "passive"))
    )
    (net (code "247") (name "unconnected-(RS13-Pad3)") (class "Default")
      (node (ref "RS13") (pin "3") (pinfunction "3_3") (pintype "passive"))
    )
    (net (code "248") (name "unconnected-(RS14-Pad1)") (class "Default")
      (node (ref "RS14") (pin "1") (pinfunction "1_1") (pintype "passive"))
    )
    (net (code "249") (name "unconnected-(RS14-Pad3)") (class "Default")
      (node (ref "RS14") (pin "3") (pinfunction "3_3") (pintype "passive"))
    )
    (net (code "250") (name "unconnected-(RS15-Pad5)") (class "Default")
      (node (ref "RS15") (pin "5") (pinfunction "5_5") (pintype "passive"))
    )
    (net (code "251") (name "unconnected-(RS15-Pad7)") (class "Default")
      (node (ref "RS15") (pin "7") (pinfunction "7_7") (pintype "passive"))
    )
    (net (code "252") (name "unconnected-(RS17-Pad2)") (class "Default")
      (node (ref "RS17") (pin "2") (pinfunction "2_2") (pintype "passive"))
    )
    (net (code "253") (name "unconnected-(RS17-Pad4)") (class "Default")
      (node (ref "RS17") (pin "4") (pinfunction "4_4") (pintype "passive"))
    )
    (net (code "254") (name "unconnected-(RS20-Pad6)") (class "Default")
      (node (ref "RS20") (pin "6") (pinfunction "6_6") (pintype "passive"))
    )
    (net (code "255") (name "unconnected-(RS20-Pad8)") (class "Default")
      (node (ref "RS20") (pin "8") (pinfunction "8_8") (pintype "passive"))
    )
    (net (code "256") (name "unconnected-(RS22-Pad1)") (class "Default")
      (node (ref "RS22") (pin "1") (pinfunction "1_1") (pintype "passive"))
    )
    (net (code "257") (name "unconnected-(RS22-Pad2)") (class "Default")
      (node (ref "RS22") (pin "2") (pinfunction "2_2") (pintype "passive"))
    )
    (net (code "258") (name "unconnected-(U1-A5-Pad6)") (class "Default")
      (node (ref "U1") (pin "6") (pinfunction "A5_6") (pintype "input+no_connect"))
    )
    (net (code "259") (name "unconnected-(U1-Y5-Pad14)") (class "Default")
      (node (ref "U1") (pin "14") (pinfunction "Y5_14") (pintype "tri_state"))
    )
    (net (code "260") (name "unconnected-(U2-A4-Pad5)") (class "Default")
      (node (ref "U2") (pin "5") (pinfunction "A4_5") (pintype "input+no_connect"))
    )
    (net (code "261") (name "unconnected-(U2-Y4-Pad15)") (class "Default")
      (node (ref "U2") (pin "15") (pinfunction "Y4_15") (pintype "tri_state"))
    )
    (net (code "262") (name "unconnected-(U3-A5-Pad6)") (class "Default")
      (node (ref "U3") (pin "6") (pinfunction "A5_6") (pintype "input+no_connect"))
    )
    (net (code "263") (name "unconnected-(U3-Y5-Pad14)") (class "Default")
      (node (ref "U3") (pin "14") (pinfunction "Y5_14") (pintype "tri_state"))
    )
    (net (code "264") (name "unconnected-(U4-A4-Pad5)") (class "Default")
      (node (ref "U4") (pin "5") (pinfunction "A4_5") (pintype "input+no_connect"))
    )
    (net (code "265") (name "unconnected-(U4-Y4-Pad15)") (class "Default")
      (node (ref "U4") (pin "15") (pinfunction "Y4_15") (pintype "tri_state"))
    )
    (net (code "266") (name "unconnected-(U5I-HSWAP_EN-Pad142)") (class "Default")
      (node (ref "U5") (pin "142") (pinfunction "HSWAP_EN_142") (pintype "input+no_connect"))
    )
    (net (code "267") (name "unconnected-(U22-NC-Pad1)") (class "Default")
      (node (ref "U22") (pin "1") (pinfunction "NC_1") (pintype "passive"))
    )
    (net (code "268") (name "unconnected-(U22-NC-Pad8)") (class "Default")
      (node (ref "U22") (pin "8") (pinfunction "NC_8") (pintype "passive"))
    )
    (net (code "269") (name "unconnected-(U22-OUTB-Pad5)") (class "Default")
      (node (ref "U22") (pin "5") (pinfunction "OUTB_5") (pintype "output"))
    )
    (net (code "270") (name "unconnected-(U24-A4-Pad5)") (class "Default")
      (node (ref "U24") (pin "5") (pinfunction "A4_5") (pintype "input+no_connect"))
    )
    (net (code "271") (name "unconnected-(U24-A5-Pad6)") (class "Default")
      (node (ref "U24") (pin "6") (pinfunction "A5_6") (pintype "input+no_connect"))
    )
    (net (code "272") (name "unconnected-(U24-Y4-Pad15)") (class "Default")
      (node (ref "U24") (pin "15") (pinfunction "Y4_15") (pintype "tri_state"))
    )
    (net (code "273") (name "unconnected-(U24-Y5-Pad14)") (class "Default")
      (node (ref "U24") (pin "14") (pinfunction "Y5_14") (pintype "tri_state"))
    )
    (net (code "274") (name "unconnected-(U27-DNC-Pad2)") (class "Default")
      (node (ref "U27") (pin "2") (pinfunction "DNC_2") (pintype "passive"))
    )
    (net (code "275") (name "unconnected-(U27-DNC-Pad9)") (class "Default")
      (node (ref "U27") (pin "9") (pinfunction "DNC_9") (pintype "passive"))
    )
    (net (code "276") (name "unconnected-(U27-DNC-Pad12)") (class "Default")
      (node (ref "U27") (pin "12") (pinfunction "DNC_12") (pintype "passive"))
    )
    (net (code "277") (name "unconnected-(U27-DNC-Pad14)") (class "Default")
      (node (ref "U27") (pin "14") (pinfunction "DNC_14") (pintype "passive"))
    )
    (net (code "278") (name "unconnected-(U27-DNC-Pad15)") (class "Default")
      (node (ref "U27") (pin "15") (pinfunction "DNC_15") (pintype "passive"))
    )
    (net (code "279") (name "unconnected-(U27-DNC-Pad16)") (class "Default")
      (node (ref "U27") (pin "16") (pinfunction "DNC_16") (pintype "passive"))
    )
    (net (code "280") (name "unconnected-(U27-~{CEO}-Pad13)") (class "Default")
      (node (ref "U27") (pin "13") (pinfunction "~{CEO}_13") (pintype "output"))
    )
    (net (code "281") (name "unconnected-(X1-E{slash}D-Pad1)") (class "Default")
      (node (ref "X1") (pin "1") (pinfunction "E/D_1") (pintype "input+no_connect"))
    )
  )
)
